# ESP32.net
KiCad netlist of a schematic drawn in EasyEDA Pro
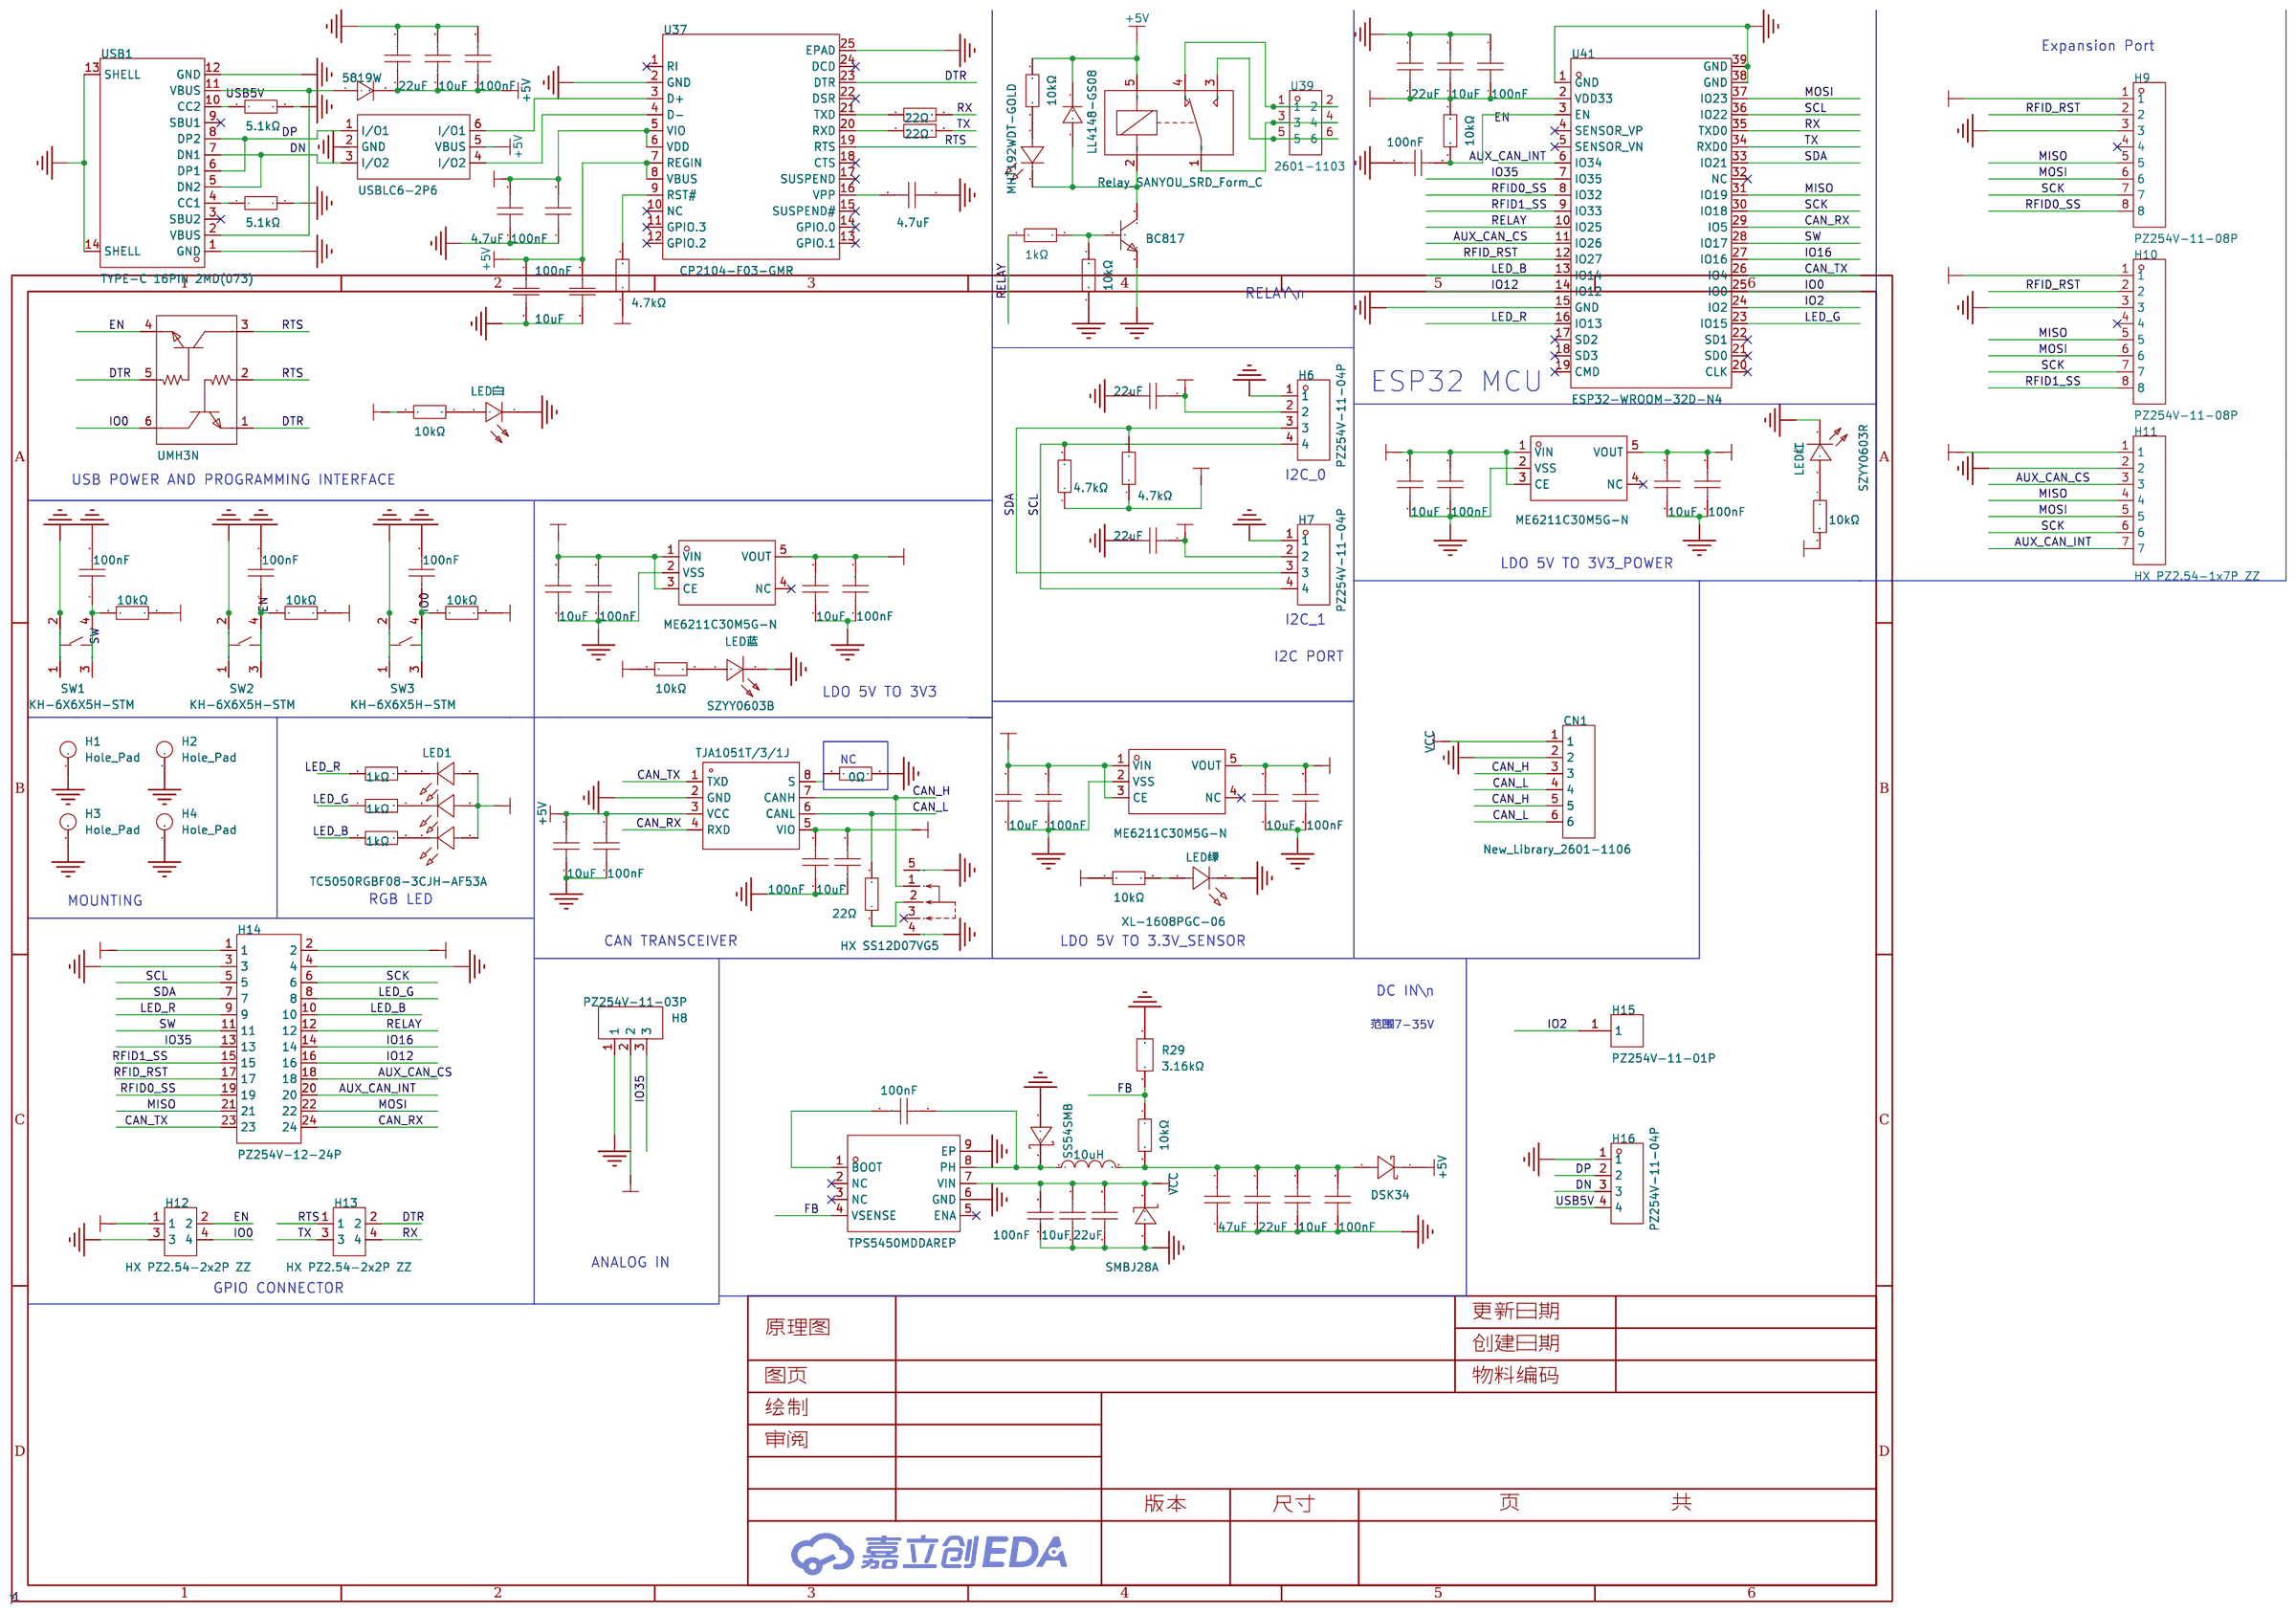
[diagram p0: schematic sheet]

(export (version "E")
  (design (tool "Eeschema 10.0.6"))
  (components
    (comp (ref "C1")
      (value "22uF")
      (footprint "easyedapro:C0805")
      (description "容值:22uF;精度:±20%;额定电压:35V;材质(温度系数):X5R;")
      (fields
        (field (name "Manufacturer Part") "CGA0805X5R226M350MT")
        (field (name "Manufacturer") "HRE(芯声)")
      )
      (libsource (lib "easyedapro") (part "CGA0805X5R226M350MT"))
    )
    (comp (ref "C2")
      (value "10uF")
      (footprint "easyedapro:C0603")
      (description "容值:10uF;精度:±20%;额定电压:25V;材质(温度系数):X5R;")
      (fields
        (field (name "Manufacturer Part") "CL10A106MA8NRNC")
        (field (name "Manufacturer") "SAMSUNG(三星)")
      )
      (libsource (lib "easyedapro") (part "CL10A106MA8NRNC"))
    )
    (comp (ref "C3")
      (value "100nF")
      (footprint "easyedapro:C0603")
      (description "容值:100nF;精度:±10%;额定电压:50V;温度系数:X7R;")
      (fields
        (field (name "Manufacturer Part") "CGA0603X7R104K500JT")
        (field (name "Manufacturer") "HRE(芯声)")
      )
      (libsource (lib "easyedapro") (part "CGA0603X7R104K500JT"))
    )
    (comp (ref "C6")
      (value "4.7uF")
      (footprint "easyedapro:C0603")
      (description "容值:4.7uF;精度:±10%;额定电压:25V;温度系数:X5R;")
      (fields
        (field (name "Manufacturer Part") "CGA0603X5R475K250JT")
        (field (name "Manufacturer") "HRE(芯声)")
      )
      (libsource (lib "easyedapro") (part "CGA0603X5R475K250JT"))
    )
    (comp (ref "C9")
      (value "100nF")
      (footprint "easyedapro:C0603")
      (description "容值:100nF;精度:±10%;额定电压:50V;温度系数:X7R;")
      (fields
        (field (name "Manufacturer Part") "CGA0603X7R104K500JT")
        (field (name "Manufacturer") "HRE(芯声)")
      )
      (libsource (lib "easyedapro") (part "CGA0603X7R104K500JT"))
    )
    (comp (ref "C10")
      (value "100nF")
      (footprint "easyedapro:C0603")
      (description "容值:100nF;精度:±10%;额定电压:50V;温度系数:X7R;")
      (fields
        (field (name "Manufacturer Part") "CGA0603X7R104K500JT")
        (field (name "Manufacturer") "HRE(芯声)")
      )
      (libsource (lib "easyedapro") (part "CGA0603X7R104K500JT"))
    )
    (comp (ref "C11")
      (value "100nF")
      (footprint "easyedapro:C0603")
      (description "容值:100nF;精度:±10%;额定电压:50V;温度系数:X7R;")
      (fields
        (field (name "Manufacturer Part") "CGA0603X7R104K500JT")
        (field (name "Manufacturer") "HRE(芯声)")
      )
      (libsource (lib "easyedapro") (part "CGA0603X7R104K500JT"))
    )
    (comp (ref "C351")
      (value "10uF")
      (footprint "easyedapro:C0603")
      (description "容值:10uF;精度:±20%;额定电压:25V;材质(温度系数):X5R;")
      (fields
        (field (name "Manufacturer Part") "CL10A106MA8NRNC")
        (field (name "Manufacturer") "SAMSUNG(三星)")
      )
      (libsource (lib "easyedapro") (part "CL10A106MA8NRNC"))
    )
    (comp (ref "C352")
      (value "10uF")
      (footprint "easyedapro:C0603")
      (description "容值:10uF;精度:±20%;额定电压:25V;材质(温度系数):X5R;")
      (fields
        (field (name "Manufacturer Part") "CL10A106MA8NRNC")
        (field (name "Manufacturer") "SAMSUNG(三星)")
      )
      (libsource (lib "easyedapro") (part "CL10A106MA8NRNC"))
    )
    (comp (ref "C353")
      (value "100nF")
      (footprint "easyedapro:C0603")
      (description "容值:100nF;精度:±10%;额定电压:50V;温度系数:X7R;")
      (fields
        (field (name "Manufacturer Part") "CGA0603X7R104K500JT")
        (field (name "Manufacturer") "HRE(芯声)")
      )
      (libsource (lib "easyedapro") (part "CGA0603X7R104K500JT"))
    )
    (comp (ref "C354")
      (value "100nF")
      (footprint "easyedapro:C0603")
      (description "容值:100nF;精度:±10%;额定电压:50V;温度系数:X7R;")
      (fields
        (field (name "Manufacturer Part") "CGA0603X7R104K500JT")
        (field (name "Manufacturer") "HRE(芯声)")
      )
      (libsource (lib "easyedapro") (part "CGA0603X7R104K500JT"))
    )
    (comp (ref "C355")
      (value "10uF")
      (footprint "easyedapro:C0603")
      (description "容值:10uF;精度:±20%;额定电压:25V;材质(温度系数):X5R;")
      (fields
        (field (name "Manufacturer Part") "CL10A106MA8NRNC")
        (field (name "Manufacturer") "SAMSUNG(三星)")
      )
      (libsource (lib "easyedapro") (part "CL10A106MA8NRNC"))
    )
    (comp (ref "C356")
      (value "100nF")
      (footprint "easyedapro:C0603")
      (description "容值:100nF;精度:±10%;额定电压:50V;温度系数:X7R;")
      (fields
        (field (name "Manufacturer Part") "CGA0603X7R104K500JT")
        (field (name "Manufacturer") "HRE(芯声)")
      )
      (libsource (lib "easyedapro") (part "CGA0603X7R104K500JT"))
    )
    (comp (ref "C357")
      (value "10uF")
      (footprint "easyedapro:C0603")
      (description "容值:10uF;精度:±20%;额定电压:25V;材质(温度系数):X5R;")
      (fields
        (field (name "Manufacturer Part") "CL10A106MA8NRNC")
        (field (name "Manufacturer") "SAMSUNG(三星)")
      )
      (libsource (lib "easyedapro") (part "CL10A106MA8NRNC"))
    )
    (comp (ref "C358")
      (value "100nF")
      (footprint "easyedapro:C0603")
      (description "容值:100nF;精度:±10%;额定电压:50V;温度系数:X7R;")
      (fields
        (field (name "Manufacturer Part") "CGA0603X7R104K500JT")
        (field (name "Manufacturer") "HRE(芯声)")
      )
      (libsource (lib "easyedapro") (part "CGA0603X7R104K500JT"))
    )
    (comp (ref "C359")
      (value "100nF")
      (footprint "easyedapro:C0603")
      (description "容值:100nF;精度:±10%;额定电压:50V;温度系数:X7R;")
      (fields
        (field (name "Manufacturer Part") "CGA0603X7R104K500JT")
        (field (name "Manufacturer") "HRE(芯声)")
      )
      (libsource (lib "easyedapro") (part "CGA0603X7R104K500JT"))
    )
    (comp (ref "C360")
      (value "4.7uF")
      (footprint "easyedapro:C0603")
      (description "容值:4.7uF;精度:±10%;额定电压:25V;温度系数:X5R;")
      (fields
        (field (name "Manufacturer Part") "CGA0603X5R475K250JT")
        (field (name "Manufacturer") "HRE(芯声)")
      )
      (libsource (lib "easyedapro") (part "CGA0603X5R475K250JT"))
    )
    (comp (ref "C361")
      (value "10uF")
      (footprint "easyedapro:C0603")
      (description "容值:10uF;精度:±20%;额定电压:25V;材质(温度系数):X5R;")
      (fields
        (field (name "Manufacturer Part") "CL10A106MA8NRNC")
        (field (name "Manufacturer") "SAMSUNG(三星)")
      )
      (libsource (lib "easyedapro") (part "CL10A106MA8NRNC"))
    )
    (comp (ref "C362")
      (value "100nF")
      (footprint "easyedapro:C0603")
      (description "容值:100nF;精度:±10%;额定电压:50V;温度系数:X7R;")
      (fields
        (field (name "Manufacturer Part") "CGA0603X7R104K500JT")
        (field (name "Manufacturer") "HRE(芯声)")
      )
      (libsource (lib "easyedapro") (part "CGA0603X7R104K500JT"))
    )
    (comp (ref "C363")
      (value "22uF")
      (footprint "easyedapro:C0805")
      (description "容值:22uF;精度:±20%;额定电压:35V;材质(温度系数):X5R;")
      (fields
        (field (name "Manufacturer Part") "CGA0805X5R226M350MT")
        (field (name "Manufacturer") "HRE(芯声)")
      )
      (libsource (lib "easyedapro") (part "CGA0805X5R226M350MT"))
    )
    (comp (ref "C364")
      (value "22uF")
      (footprint "easyedapro:C0805")
      (description "容值:22uF;精度:±20%;额定电压:35V;材质(温度系数):X5R;")
      (fields
        (field (name "Manufacturer Part") "CGA0805X5R226M350MT")
        (field (name "Manufacturer") "HRE(芯声)")
      )
      (libsource (lib "easyedapro") (part "CGA0805X5R226M350MT"))
    )
    (comp (ref "C369")
      (value "10uF")
      (footprint "easyedapro:C0603")
      (description "容值:10uF;精度:±20%;额定电压:25V;材质(温度系数):X5R;")
      (fields
        (field (name "Manufacturer Part") "CL10A106MA8NRNC")
        (field (name "Manufacturer") "SAMSUNG(三星)")
      )
      (libsource (lib "easyedapro") (part "CL10A106MA8NRNC"))
    )
    (comp (ref "C370")
      (value "10uF")
      (footprint "easyedapro:C0603")
      (description "容值:10uF;精度:±20%;额定电压:25V;材质(温度系数):X5R;")
      (fields
        (field (name "Manufacturer Part") "CL10A106MA8NRNC")
        (field (name "Manufacturer") "SAMSUNG(三星)")
      )
      (libsource (lib "easyedapro") (part "CL10A106MA8NRNC"))
    )
    (comp (ref "C371")
      (value "100nF")
      (footprint "easyedapro:C0603")
      (description "容值:100nF;精度:±10%;额定电压:50V;温度系数:X7R;")
      (fields
        (field (name "Manufacturer Part") "CGA0603X7R104K500JT")
        (field (name "Manufacturer") "HRE(芯声)")
      )
      (libsource (lib "easyedapro") (part "CGA0603X7R104K500JT"))
    )
    (comp (ref "C372")
      (value "100nF")
      (footprint "easyedapro:C0603")
      (description "容值:100nF;精度:±10%;额定电压:50V;温度系数:X7R;")
      (fields
        (field (name "Manufacturer Part") "CGA0603X7R104K500JT")
        (field (name "Manufacturer") "HRE(芯声)")
      )
      (libsource (lib "easyedapro") (part "CGA0603X7R104K500JT"))
    )
    (comp (ref "C373")
      (value "10uF")
      (footprint "easyedapro:C0603")
      (description "容值:10uF;精度:±20%;额定电压:25V;材质(温度系数):X5R;")
      (fields
        (field (name "Manufacturer Part") "CL10A106MA8NRNC")
        (field (name "Manufacturer") "SAMSUNG(三星)")
      )
      (libsource (lib "easyedapro") (part "CL10A106MA8NRNC"))
    )
    (comp (ref "C374")
      (value "100nF")
      (footprint "easyedapro:C0603")
      (description "容值:100nF;精度:±10%;额定电压:50V;温度系数:X7R;")
      (fields
        (field (name "Manufacturer Part") "CGA0603X7R104K500JT")
        (field (name "Manufacturer") "HRE(芯声)")
      )
      (libsource (lib "easyedapro") (part "CGA0603X7R104K500JT"))
    )
    (comp (ref "C375")
      (value "100nF")
      (footprint "easyedapro:C0603")
      (description "容值:100nF;精度:±10%;额定电压:50V;温度系数:X7R;")
      (fields
        (field (name "Manufacturer Part") "CGA0603X7R104K500JT")
        (field (name "Manufacturer") "HRE(芯声)")
      )
      (libsource (lib "easyedapro") (part "CGA0603X7R104K500JT"))
    )
    (comp (ref "C376")
      (value "10uF")
      (footprint "easyedapro:C0603")
      (description "容值:10uF;精度:±20%;额定电压:25V;材质(温度系数):X5R;")
      (fields
        (field (name "Manufacturer Part") "CL10A106MA8NRNC")
        (field (name "Manufacturer") "SAMSUNG(三星)")
      )
      (libsource (lib "easyedapro") (part "CL10A106MA8NRNC"))
    )
    (comp (ref "C377")
      (value "22uF")
      (footprint "easyedapro:C0805")
      (description "容值:22uF;精度:±20%;额定电压:35V;材质(温度系数):X5R;")
      (fields
        (field (name "Manufacturer Part") "CGA0805X5R226M350MT")
        (field (name "Manufacturer") "HRE(芯声)")
      )
      (libsource (lib "easyedapro") (part "CGA0805X5R226M350MT"))
    )
    (comp (ref "C378")
      (value "10uF")
      (footprint "easyedapro:C0603")
      (description "容值:10uF;精度:±20%;额定电压:25V;材质(温度系数):X5R;")
      (fields
        (field (name "Manufacturer Part") "CL10A106MA8NRNC")
        (field (name "Manufacturer") "SAMSUNG(三星)")
      )
      (libsource (lib "easyedapro") (part "CL10A106MA8NRNC"))
    )
    (comp (ref "C379")
      (value "100nF")
      (footprint "easyedapro:C0603")
      (description "容值:100nF;精度:±10%;额定电压:50V;温度系数:X7R;")
      (fields
        (field (name "Manufacturer Part") "CGA0603X7R104K500JT")
        (field (name "Manufacturer") "HRE(芯声)")
      )
      (libsource (lib "easyedapro") (part "CGA0603X7R104K500JT"))
    )
    (comp (ref "C380")
      (value "100nF")
      (footprint "easyedapro:C0603")
      (description "容值:100nF;精度:±10%;额定电压:50V;温度系数:X7R;")
      (fields
        (field (name "Manufacturer Part") "CGA0603X7R104K500JT")
        (field (name "Manufacturer") "HRE(芯声)")
      )
      (libsource (lib "easyedapro") (part "CGA0603X7R104K500JT"))
    )
    (comp (ref "C382")
      (value "10uF")
      (footprint "easyedapro:C1206")
      (description "容值:10uF;精度:±10%;额定电压:50V;温度系数:X5R;")
      (fields
        (field (name "Manufacturer Part") "HGC1206R5106K500NSPJ")
        (field (name "Manufacturer") "Chinocera(华瓷)")
      )
      (libsource (lib "easyedapro") (part "HGC1206R5106K500NSPJ"))
    )
    (comp (ref "C383")
      (value "22uF")
      (footprint "easyedapro:C1206")
      (description "容值:22uF;精度:±20%;额定电压:35V;温度系数:X5R;")
      (fields
        (field (name "Manufacturer Part") "CGA1206X5R226M350NT")
        (field (name "Manufacturer") "HRE(芯声)")
      )
      (libsource (lib "easyedapro") (part "CGA1206X5R226M350NT"))
    )
    (comp (ref "C384")
      (value "100nF")
      (footprint "easyedapro:C1206")
      (description "容值:100nF;精度:±10%;额定电压:50V;材质(温度系数):X7R;")
      (fields
        (field (name "Manufacturer Part") "CL31B104KBCNNNC")
        (field (name "Manufacturer") "SAMSUNG(三星)")
      )
      (libsource (lib "easyedapro") (part "CL31B104KBCNNNC"))
    )
    (comp (ref "C385")
      (value "47uF")
      (footprint "easyedapro:C1206")
      (description "容值:47uF;精度:±20%;额定电压:25V;温度系数:X5R;")
      (fields
        (field (name "Manufacturer Part") "HGC1206R5476M250NSPJ")
        (field (name "Manufacturer") "Chinocera(华瓷)")
      )
      (libsource (lib "easyedapro") (part "HGC1206R5476M250NSPJ"))
    )
    (comp (ref "C386")
      (value "22uF")
      (footprint "easyedapro:C0805")
      (description "容值:22uF;精度:±20%;额定电压:35V;材质(温度系数):X5R;")
      (fields
        (field (name "Manufacturer Part") "CGA0805X5R226M350MT")
        (field (name "Manufacturer") "HRE(芯声)")
      )
      (libsource (lib "easyedapro") (part "CGA0805X5R226M350MT"))
    )
    (comp (ref "C387")
      (value "10uF")
      (footprint "easyedapro:C0603")
      (description "容值:10uF;精度:±20%;额定电压:25V;材质(温度系数):X5R;")
      (fields
        (field (name "Manufacturer Part") "CL10A106MA8NRNC")
        (field (name "Manufacturer") "SAMSUNG(三星)")
      )
      (libsource (lib "easyedapro") (part "CL10A106MA8NRNC"))
    )
    (comp (ref "C388")
      (value "100nF")
      (footprint "easyedapro:C0603")
      (description "容值:100nF;精度:±10%;额定电压:50V;温度系数:X7R;")
      (fields
        (field (name "Manufacturer Part") "CGA0603X7R104K500JT")
        (field (name "Manufacturer") "HRE(芯声)")
      )
      (libsource (lib "easyedapro") (part "CGA0603X7R104K500JT"))
    )
    (comp (ref "C389")
      (value "100nF")
      (footprint "easyedapro:C0603")
      (description "容值:100nF;精度:±10%;额定电压:50V;温度系数:X7R;")
      (fields
        (field (name "Manufacturer Part") "CGA0603X7R104K500JT")
        (field (name "Manufacturer") "HRE(芯声)")
      )
      (libsource (lib "easyedapro") (part "CGA0603X7R104K500JT"))
    )
    (comp (ref "CN1")
      (value "New_Library_2601-1106")
      (footprint "easyedapro:CONN-TH_2601-1106")
      (fields (field (name "Manufacturer Part") "2601-1106"))
      (libsource (lib "easyedapro") (part "2601-1106"))
    )
    (comp (ref "D1")
      (value "USBLC6-2P6")
      (footprint "easyedapro:SOT-666-6_L1.6-W1.2-P0.50-LS1.6-BL")
      (description "极性:单向;反向截止电压(Vrwm):5V;最大钳位电压:14V;峰值脉冲电流(Ipp):5.5A;峰值脉冲功率(Ppp):80W;击穿电压:6V;")
      (fields (field (name "Manufacturer") "TECH PUBLIC(台舟)"))
      (libsource (lib "easyedapro") (part "USBLC6-2P6_C2827693"))
    )
    (comp (ref "D2")
      (value "5819W")
      (footprint "easyedapro:SOD-123_L2.7-W1.6-LS3.7-FD")
      (description "正向压降(Vf):900mV@3A;直流反向耐压(Vr):40V;整流电流:1A;")
      (fields (field (name "Manufacturer") "MOT(仁懋)"))
      (libsource (lib "easyedapro") (part "5819W"))
    )
    (comp (ref "D3")
      (value "LL4148-GS08")
      (footprint "easyedapro:SOD-80_L3.5-W1.5-RD")
      (description "二极管配置:-;正向压降(Vf):860mV@50mA;直流反向耐压(Vr):75V;整流电流:300mA;反向恢复时间(Trr):-;")
      (fields (field (name "Manufacturer") "VISHAY(威世)"))
      (libsource (lib "easyedapro") (part "LL4148-GS08"))
    )
    (comp (ref "D5")
      (value "SS54SMB")
      (footprint "easyedapro:SMB_L4.6-W3.6-LS5.3-RD")
      (description "schottky,5A 40V VF&lt;0.55V DO-214AA SMB")
      (fields (field (name "Manufacturer") "BORN(伯恩半导体)"))
      (libsource (lib "easyedapro") (part "SS54SMB"))
    )
    (comp (ref "D6")
      (value "SMBJ28A")
      (footprint "easyedapro:SMB_L4.6-W3.6-LS5.3-L-FD")
      (description "极性:Unidirectional;峰值脉冲电流（10/1000us）:13.2A;箝位电压:45.4V;击穿电压（最小值）:31.1V;反向关断电压（典型值）:28V;")
      (fields (field (name "Manufacturer") "JJW(捷捷微)"))
      (libsource (lib "easyedapro") (part "SMBJ28A_C356769"))
    )
    (comp (ref "D7")
      (value "DSK34")
      (footprint "easyedapro:SOD-123FL_L2.7-W1.8-LS3.8-RD")
      (description "二极管配置:独立式;正向压降(Vf):550mV@3A;直流反向耐压(Vr):40V;平均整流电流(Io):3A;")
      (fields (field (name "Manufacturer") "宏迦橙"))
      (libsource (lib "easyedapro") (part "DSK34_C7502709"))
    )
    (comp (ref "H1")
      (value "Hole_Pad")
      (footprint "easyedapro:MountingHole:MountingHole_3.2mm_M3_Pad_Via")
      (description "Mounting Hole with connection")
      (libsource (lib "easyedapro") (part "Mechanical_MountingHole_Pad"))
    )
    (comp (ref "H2")
      (value "Hole_Pad")
      (footprint "easyedapro:MountingHole:MountingHole_3.2mm_M3_Pad_Via")
      (description "Mounting Hole with connection")
      (libsource (lib "easyedapro") (part "Mechanical_MountingHole_Pad"))
    )
    (comp (ref "H3")
      (value "Hole_Pad")
      (footprint "easyedapro:MountingHole:MountingHole_3.2mm_M3_Pad_Via")
      (description "Mounting Hole with connection")
      (libsource (lib "easyedapro") (part "Mechanical_MountingHole_Pad"))
    )
    (comp (ref "H4")
      (value "Hole_Pad")
      (footprint "easyedapro:MountingHole:MountingHole_3.2mm_M3_Pad_Via")
      (description "Mounting Hole with connection")
      (libsource (lib "easyedapro") (part "Mechanical_MountingHole_Pad"))
    )
    (comp (ref "H6")
      (value "PZ254V-11-04P")
      (footprint "easyedapro:HDR-TH_4P-P2.54-V-M")
      (fields (field (name "Manufacturer") "XFCN(兴飞)"))
      (libsource (lib "easyedapro") (part "PZ254V-11-04P_C2691448"))
    )
    (comp (ref "H7")
      (value "PZ254V-11-04P")
      (footprint "easyedapro:HDR-TH_4P-P2.54-V-M")
      (fields (field (name "Manufacturer") "XFCN(兴飞)"))
      (libsource (lib "easyedapro") (part "PZ254V-11-04P_C2691448"))
    )
    (comp (ref "H8")
      (value "PZ254V-11-03P")
      (footprint "easyedapro:HDR-TH_3P-P2.54-V-M")
      (fields (field (name "Manufacturer") "XFCN(兴飞)"))
      (libsource (lib "easyedapro") (part "PZ254V-11-03P_C2937625"))
    )
    (comp (ref "H9")
      (value "PZ254V-11-08P")
      (footprint "easyedapro:HDR-TH_8P-P2.54-V-M")
      (fields (field (name "Manufacturer") "XFCN(兴飞)"))
      (libsource (lib "easyedapro") (part "PZ254V-11-08P"))
    )
    (comp (ref "H10")
      (value "PZ254V-11-08P")
      (footprint "easyedapro:HDR-TH_8P-P2.54-V-M")
      (fields (field (name "Manufacturer") "XFCN(兴飞)"))
      (libsource (lib "easyedapro") (part "PZ254V-11-08P"))
    )
    (comp (ref "H11")
      (value "HX PZ2.54-1x7P ZZ")
      (footprint "easyedapro:HDR-TH_7P-P2.54-V-M")
      (fields (field (name "Manufacturer") "hanxia(韩下)"))
      (libsource (lib "easyedapro") (part "HX PZ2.54-1X7P ZZ"))
    )
    (comp (ref "H12")
      (value "HX PZ2.54-2x2P ZZ")
      (footprint "easyedapro:HDR-TH_HX-PZ2.54-2X2P-ZZ")
      (fields (field (name "Manufacturer") "hanxia(韩下)"))
      (libsource (lib "easyedapro") (part "HX PZ2.54-2X2P ZZ"))
    )
    (comp (ref "H13")
      (value "HX PZ2.54-2x2P ZZ")
      (footprint "easyedapro:HDR-TH_HX-PZ2.54-2X2P-ZZ")
      (fields (field (name "Manufacturer") "hanxia(韩下)"))
      (libsource (lib "easyedapro") (part "HX PZ2.54-2X2P ZZ"))
    )
    (comp (ref "H14")
      (value "PZ254V-12-24P")
      (footprint "easyedapro:HDR-TH_24P-P2.54-V-M-R2-C12-S2.54")
      (fields (field (name "Manufacturer") "XFCN(兴飞)"))
      (libsource (lib "easyedapro") (part "PZ254V-12-24P"))
    )
    (comp (ref "H15")
      (value "PZ254V-11-01P")
      (footprint "easyedapro:HDR-TH_1P-P2.54-V-M")
      (fields (field (name "Manufacturer") "XFCN(兴飞)"))
      (libsource (lib "easyedapro") (part "PZ254V-11-01P"))
    )
    (comp (ref "H16")
      (value "PZ254V-11-04P")
      (footprint "easyedapro:HDR-TH_4P-P2.54-V-M")
      (fields (field (name "Manufacturer") "XFCN(兴飞)"))
      (libsource (lib "easyedapro") (part "PZ254V-11-04P_C2691448"))
    )
    (comp (ref "K1")
      (value "SANYOU_SRD_Form_C")
      (footprint "easyedapro:Relay_THT:Relay_SPDT_SANYOU_SRD_Series_Form_C")
      (libsource (lib "easyedapro") (part "Relay_SANYOU_SRD_Form_C"))
    )
    (comp (ref "L12")
      (value "10uH")
      (footprint "easyedapro:IND-SMD_L5.4-W5.2_FXL0530")
      (description "电感值:10uH;精度:±20%;额定电流:3.2A;饱和电流(Isat):3.5A;类型:一体成型电感;")
      (fields (field (name "Manufacturer Part") "FXL0530-100-M") (field (name "Manufacturer") "cjiang(长江微电)"))
      (libsource (lib "easyedapro") (part "FXL0530-100-M"))
    )
    (comp (ref "LED1")
      (value "TC5050RGBF08-3CJH-AF53A")
      (footprint "easyedapro:LED-SMD_6P-L5.0-W5.0-TL_TC5050RGBF08")
      (description "5050RGB，0.2W 20mA")
      (fields (field (name "Manufacturer") "TCWIN(天成)"))
      (libsource (lib "easyedapro") (part "TC5050RGBF08-3CJH-AF53A"))
    )
    (comp (ref "LED白")
      (value "NCD0603W1")
      (footprint "easyedapro:LED0603-RD")
      (fields (field (name "Manufacturer") "国星光电"))
      (libsource (lib "easyedapro") (part "NCD0603W1"))
    )
    (comp (ref "LED红")
      (value "SZYY0603R")
      (footprint "easyedapro:LED0603-R-RD")
      (fields (field (name "Manufacturer") "yongyu(永裕光电)"))
      (libsource (lib "easyedapro") (part "SZYY0603R"))
    )
    (comp (ref "LED绿")
      (value "XL-1608PGC-06")
      (footprint "easyedapro:LED0603-RD_GREEN")
      (fields (field (name "Manufacturer") "XINGLIGHT(成兴光)"))
      (libsource (lib "easyedapro") (part "XL-1608PGC-06"))
    )
    (comp (ref "LED蓝")
      (value "SZYY0603B")
      (footprint "easyedapro:LED0603-R-RD_BLUE")
      (fields (field (name "Manufacturer") "yongyu(永裕光电)"))
      (libsource (lib "easyedapro") (part "SZYY0603B"))
    )
    (comp (ref "Q1")
      (value "UMH3N")
      (footprint "easyedapro:SC-70-6_L2.2-W1.3-P0.65-LS2.1-BR")
      (description "晶体管类型:-;集射极击穿电压(Vceo):50V;集电极电流(Ic):100mA;耗散功率(Pd):150mW;直流电流增益(hFE):100@1mA,5V;")
      (fields (field (name "Manufacturer") "CJ(江苏长电/长晶)"))
      (libsource (lib "easyedapro") (part "UMH3N"))
    )
    (comp (ref "Q2")
      (value "BC817")
      (footprint "easyedapro:SOT-23-3_L2.9-W1.3-P1.90-LS2.4-BR")
      (description "晶体管类型:NPN;集电极电流(Ic):500mA;集射极击穿电压(Vceo):45V;耗散功率(Pd):300mW;直流电流增益(hFE):-;")
      (fields (field (name "Manufacturer") "JSMSEMI(杰盛微)"))
      (libsource (lib "easyedapro") (part "BC817_C916383"))
    )
    (comp (ref "R1")
      (value "5.1kΩ")
      (footprint "easyedapro:R0603")
      (description "电阻类型:厚膜电阻;阻值:5.1kΩ;精度:±1%;功率:100mW;最大工作电压:75V;温度系数:±100ppm/°C;")
      (fields
        (field (name "Manufacturer Part") "0603WAF5101T5E")
        (field (name "Manufacturer") "UNI-ROYAL(厚声)")
      )
      (libsource (lib "easyedapro") (part "0603WAF5101T5E"))
    )
    (comp (ref "R2")
      (value "5.1kΩ")
      (footprint "easyedapro:R0603")
      (description "电阻类型:厚膜电阻;阻值:5.1kΩ;精度:±1%;功率:100mW;最大工作电压:75V;温度系数:±100ppm/°C;")
      (fields
        (field (name "Manufacturer Part") "0603WAF5101T5E")
        (field (name "Manufacturer") "UNI-ROYAL(厚声)")
      )
      (libsource (lib "easyedapro") (part "0603WAF5101T5E"))
    )
    (comp (ref "R4")
      (value "22Ω")
      (footprint "easyedapro:R0603")
      (description "电阻类型:厚膜电阻;阻值:22Ω;精度:±1%;功率:100mW;最大工作电压:75V;温度系数:±100ppm/°C;")
      (fields
        (field (name "Manufacturer Part") "0603WAF220JT5E")
        (field (name "Manufacturer") "UNI-ROYAL(厚声)")
      )
      (libsource (lib "easyedapro") (part "0603WAF220JT5E"))
    )
    (comp (ref "R5")
      (value "22Ω")
      (footprint "easyedapro:R0603")
      (description "电阻类型:厚膜电阻;阻值:22Ω;精度:±1%;功率:100mW;最大工作电压:75V;温度系数:±100ppm/°C;")
      (fields
        (field (name "Manufacturer Part") "0603WAF220JT5E")
        (field (name "Manufacturer") "UNI-ROYAL(厚声)")
      )
      (libsource (lib "easyedapro") (part "0603WAF220JT5E"))
    )
    (comp (ref "R7")
      (value "10kΩ")
      (footprint "easyedapro:R0603")
      (description "电阻类型:厚膜电阻;阻值:10kΩ;精度:±1%;功率:100mW;工作电压:75V;温度系数:±100ppm/°C;")
      (fields
        (field (name "Manufacturer Part") "0603WAF1002T5E")
        (field (name "Manufacturer") "UNI-ROYAL(厚声)")
      )
      (libsource (lib "easyedapro") (part "0603WAF1002T5E"))
    )
    (comp (ref "R8")
      (value "10kΩ")
      (footprint "easyedapro:R0603")
      (description "电阻类型:厚膜电阻;阻值:10kΩ;精度:±1%;功率:100mW;工作电压:75V;温度系数:±100ppm/°C;")
      (fields
        (field (name "Manufacturer Part") "0603WAF1002T5E")
        (field (name "Manufacturer") "UNI-ROYAL(厚声)")
      )
      (libsource (lib "easyedapro") (part "0603WAF1002T5E"))
    )
    (comp (ref "R9")
      (value "10kΩ")
      (footprint "easyedapro:R0603")
      (description "电阻类型:厚膜电阻;阻值:10kΩ;精度:±1%;功率:100mW;工作电压:75V;温度系数:±100ppm/°C;")
      (fields
        (field (name "Manufacturer Part") "0603WAF1002T5E")
        (field (name "Manufacturer") "UNI-ROYAL(厚声)")
      )
      (libsource (lib "easyedapro") (part "0603WAF1002T5E"))
    )
    (comp (ref "R10")
      (value "10kΩ")
      (footprint "easyedapro:R0603")
      (description "电阻类型:厚膜电阻;阻值:10kΩ;精度:±1%;功率:100mW;工作电压:75V;温度系数:±100ppm/°C;")
      (fields
        (field (name "Manufacturer Part") "0603WAF1002T5E")
        (field (name "Manufacturer") "UNI-ROYAL(厚声)")
      )
      (libsource (lib "easyedapro") (part "0603WAF1002T5E"))
    )
    (comp (ref "R11")
      (value "10kΩ")
      (footprint "easyedapro:R0603")
      (description "电阻类型:厚膜电阻;阻值:10kΩ;精度:±1%;功率:100mW;工作电压:75V;温度系数:±100ppm/°C;")
      (fields
        (field (name "Manufacturer Part") "0603WAF1002T5E")
        (field (name "Manufacturer") "UNI-ROYAL(厚声)")
      )
      (libsource (lib "easyedapro") (part "0603WAF1002T5E"))
    )
    (comp (ref "R12")
      (value "1kΩ")
      (footprint "easyedapro:R0603")
      (description "电阻类型:厚膜电阻;阻值:1kΩ;精度:±1%;功率:100mW;最大工作电压:75V;温度系数:±100ppm/°C;")
      (fields
        (field (name "Manufacturer Part") "0603WAF1001T5E")
        (field (name "Manufacturer") "UNI-ROYAL(厚声)")
      )
      (libsource (lib "easyedapro") (part "0603WAF1001T5E"))
    )
    (comp (ref "R13")
      (value "1kΩ")
      (footprint "easyedapro:R0603")
      (description "电阻类型:厚膜电阻;阻值:1kΩ;精度:±1%;功率:100mW;最大工作电压:75V;温度系数:±100ppm/°C;")
      (fields
        (field (name "Manufacturer Part") "0603WAF1001T5E")
        (field (name "Manufacturer") "UNI-ROYAL(厚声)")
      )
      (libsource (lib "easyedapro") (part "0603WAF1001T5E"))
    )
    (comp (ref "R14")
      (value "1kΩ")
      (footprint "easyedapro:R0603")
      (description "电阻类型:厚膜电阻;阻值:1kΩ;精度:±1%;功率:100mW;最大工作电压:75V;温度系数:±100ppm/°C;")
      (fields
        (field (name "Manufacturer Part") "0603WAF1001T5E")
        (field (name "Manufacturer") "UNI-ROYAL(厚声)")
      )
      (libsource (lib "easyedapro") (part "0603WAF1001T5E"))
    )
    (comp (ref "R15")
      (value "0Ω")
      (footprint "easyedapro:R0603")
      (description "电阻类型:厚膜电阻;阻值:0Ω;精度:±1%;功率:100mW;最大工作电压:75V;")
      (fields
        (field (name "Manufacturer Part") "0603WAF0000T5E")
        (field (name "Manufacturer") "UNI-ROYAL(厚声)")
      )
      (libsource (lib "easyedapro") (part "0603WAF0000T5E"))
    )
    (comp (ref "R16")
      (value "22Ω")
      (footprint "easyedapro:R0603")
      (description "电阻类型:厚膜电阻;阻值:22Ω;精度:±1%;功率:100mW;最大工作电压:75V;温度系数:±100ppm/°C;")
      (fields
        (field (name "Manufacturer Part") "0603WAF220JT5E")
        (field (name "Manufacturer") "UNI-ROYAL(厚声)")
      )
      (libsource (lib "easyedapro") (part "0603WAF220JT5E"))
    )
    (comp (ref "R17")
      (value "4.7kΩ")
      (footprint "easyedapro:R0603")
      (description "电阻类型:厚膜电阻;阻值:4.7kΩ;精度:±1%;功率:100mW;最大工作电压:75V;温度系数:±100ppm/°C;")
      (fields
        (field (name "Manufacturer Part") "0603WAF4701T5E")
        (field (name "Manufacturer") "UNI-ROYAL(厚声)")
      )
      (libsource (lib "easyedapro") (part "0603WAF4701T5E"))
    )
    (comp (ref "R18")
      (value "10kΩ")
      (footprint "easyedapro:R0603")
      (description "电阻类型:厚膜电阻;阻值:10kΩ;精度:±1%;功率:100mW;工作电压:75V;温度系数:±100ppm/°C;")
      (fields
        (field (name "Manufacturer Part") "0603WAF1002T5E")
        (field (name "Manufacturer") "UNI-ROYAL(厚声)")
      )
      (libsource (lib "easyedapro") (part "0603WAF1002T5E"))
    )
    (comp (ref "R19")
      (value "10kΩ")
      (footprint "easyedapro:R0603")
      (description "电阻类型:厚膜电阻;阻值:10kΩ;精度:±1%;功率:100mW;工作电压:75V;温度系数:±100ppm/°C;")
      (fields
        (field (name "Manufacturer Part") "0603WAF1002T5E")
        (field (name "Manufacturer") "UNI-ROYAL(厚声)")
      )
      (libsource (lib "easyedapro") (part "0603WAF1002T5E"))
    )
    (comp (ref "R20")
      (value "1kΩ")
      (footprint "easyedapro:R0603")
      (description "电阻类型:厚膜电阻;阻值:1kΩ;精度:±1%;功率:100mW;最大工作电压:75V;温度系数:±100ppm/°C;")
      (fields
        (field (name "Manufacturer Part") "0603WAF1001T5E")
        (field (name "Manufacturer") "UNI-ROYAL(厚声)")
      )
      (libsource (lib "easyedapro") (part "0603WAF1001T5E"))
    )
    (comp (ref "R21")
      (value "4.7kΩ")
      (footprint "easyedapro:R0603")
      (description "电阻类型:厚膜电阻;阻值:4.7kΩ;精度:±1%;功率:100mW;最大工作电压:75V;温度系数:±100ppm/°C;")
      (fields
        (field (name "Manufacturer Part") "0603WAF4701T5E")
        (field (name "Manufacturer") "UNI-ROYAL(厚声)")
      )
      (libsource (lib "easyedapro") (part "0603WAF4701T5E"))
    )
    (comp (ref "R22")
      (value "4.7kΩ")
      (footprint "easyedapro:R0603")
      (description "电阻类型:厚膜电阻;阻值:4.7kΩ;精度:±1%;功率:100mW;最大工作电压:75V;温度系数:±100ppm/°C;")
      (fields
        (field (name "Manufacturer Part") "0603WAF4701T5E")
        (field (name "Manufacturer") "UNI-ROYAL(厚声)")
      )
      (libsource (lib "easyedapro") (part "0603WAF4701T5E"))
    )
    (comp (ref "R23")
      (value "10kΩ")
      (footprint "easyedapro:R0603")
      (description "电阻类型:厚膜电阻;阻值:10kΩ;精度:±1%;功率:100mW;工作电压:75V;温度系数:±100ppm/°C;")
      (fields
        (field (name "Manufacturer Part") "0603WAF1002T5E")
        (field (name "Manufacturer") "UNI-ROYAL(厚声)")
      )
      (libsource (lib "easyedapro") (part "0603WAF1002T5E"))
    )
    (comp (ref "R24")
      (value "10kΩ")
      (footprint "easyedapro:R0603")
      (description "电阻类型:厚膜电阻;阻值:10kΩ;精度:±1%;功率:100mW;工作电压:75V;温度系数:±100ppm/°C;")
      (fields
        (field (name "Manufacturer Part") "0603WAF1002T5E")
        (field (name "Manufacturer") "UNI-ROYAL(厚声)")
      )
      (libsource (lib "easyedapro") (part "0603WAF1002T5E"))
    )
    (comp (ref "R25")
      (value "10kΩ")
      (footprint "easyedapro:R0603")
      (description "电阻类型:厚膜电阻;阻值:10kΩ;精度:±1%;功率:100mW;工作电压:75V;温度系数:±100ppm/°C;")
      (fields
        (field (name "Manufacturer Part") "0603WAF1002T5E")
        (field (name "Manufacturer") "UNI-ROYAL(厚声)")
      )
      (libsource (lib "easyedapro") (part "0603WAF1002T5E"))
    )
    (comp (ref "R28")
      (value "10kΩ")
      (footprint "easyedapro:R0603")
      (description "电阻类型:厚膜电阻;阻值:10kΩ;精度:±1%;功率:100mW;工作电压:75V;温度系数:±100ppm/°C;")
      (fields
        (field (name "Manufacturer Part") "0603WAF1002T5E")
        (field (name "Manufacturer") "UNI-ROYAL(厚声)")
      )
      (libsource (lib "easyedapro") (part "0603WAF1002T5E"))
    )
    (comp (ref "R29")
      (value "3.16kΩ")
      (footprint "easyedapro:R0603")
      (description "电阻类型:厚膜电阻;阻值:3.16kΩ;精度:±1%;功率:100mW;最大工作电压:75V;温度系数:±100ppm/°C;")
      (fields (field (name "Manufacturer Part") "FRC0603F3161TS") (field (name "Manufacturer") "FOJAN(富捷)"))
      (libsource (lib "easyedapro") (part "FRC0603F3161TS"))
    )
    (comp (ref "SW1")
      (value "KH-6X6X5H-STM")
      (footprint "easyedapro:SW-SMD_4P-L6.0-W6.0-P4.50-LS9.0_H5.0")
      (description "电路结构:单刀单掷;按钮形状:圆形按钮;安装方式:立贴;开关长度:6mm;开关宽度:6mm;开关高度:5mm;带支架:不带;触点电流:50mA;额定电压(DC):12V;机械寿命:8万次;")
      (fields (field (name "Manufacturer") "kinghelm(金航标)"))
      (libsource (lib "easyedapro") (part "KH-6X6X5H-STM"))
    )
    (comp (ref "SW2")
      (value "KH-6X6X5H-STM")
      (footprint "easyedapro:SW-SMD_4P-L6.0-W6.0-P4.50-LS9.0_H5.0")
      (description "电路结构:单刀单掷;按钮形状:圆形按钮;安装方式:立贴;开关长度:6mm;开关宽度:6mm;开关高度:5mm;带支架:不带;触点电流:50mA;额定电压(DC):12V;机械寿命:8万次;")
      (fields (field (name "Manufacturer") "kinghelm(金航标)"))
      (libsource (lib "easyedapro") (part "KH-6X6X5H-STM"))
    )
    (comp (ref "SW3")
      (value "KH-6X6X5H-STM")
      (footprint "easyedapro:SW-SMD_4P-L6.0-W6.0-P4.50-LS9.0_H5.0")
      (description "电路结构:单刀单掷;按钮形状:圆形按钮;安装方式:立贴;开关长度:6mm;开关宽度:6mm;开关高度:5mm;带支架:不带;触点电流:50mA;额定电压(DC):12V;机械寿命:8万次;")
      (fields (field (name "Manufacturer") "kinghelm(金航标)"))
      (libsource (lib "easyedapro") (part "KH-6X6X5H-STM"))
    )
    (comp (ref "U31")
      (value "ME6211C30M5G-N")
      (footprint "easyedapro:SOT-23-5_L2.9-W1.6-P0.95-LS2.8-BL")
      (description "输出类型:固定;最大输入电压:6V;输出电压:3V;最大输出电流:500mA;电源纹波抑制比(PSRR):-;输出极性:正极;")
      (fields (field (name "Manufacturer") "MICRONE(南京微盟)"))
      (libsource (lib "easyedapro") (part "ME6211C30M5G-N"))
    )
    (comp (ref "U34")
      (value "TJA1051T/3/1J")
      (footprint "easyedapro:SOIC-8_L4.9-W3.9-P1.27-LS6.0-BL")
      (description "类型:-;数据速率:5Mbps;")
      (fields (field (name "Manufacturer") "NXP(恩智浦)"))
      (libsource (lib "easyedapro") (part "TJA1051T/3/1J"))
    )
    (comp (ref "U36")
      (value "HX SS12D07VG5")
      (footprint "easyedapro:SW-TH_SS12D07VG3")
      (description "电路结构:单刀双掷;安装方式:直插;开关颜色:黑色;额定电流:300mA;额定电压:50V;工作寿命:1万次;")
      (fields (field (name "Manufacturer") "hanxia(韩下)"))
      (libsource (lib "easyedapro") (part "HX SS12D07VG5"))
    )
    (comp (ref "U37")
      (value "CP2104-F03-GMR")
      (footprint "easyedapro:QFN-24_L4.0-W4.0-P0.50-BL-EP2.7")
      (description "应用功能:USB转UART;接口协议:-;数据速率:2Mbps;")
      (fields (field (name "Manufacturer") "SKYWORKS/SILICON LABS(芯科)"))
      (libsource (lib "easyedapro") (part "CP2104-F03-GM"))
    )
    (comp (ref "U38")
      (value "MHT192WDT-GOLD")
      (footprint "easyedapro:LED0603-RD-YELLOW")
      (description "发光颜色:黄色;功率:60mW;正向电流:5mA;主波长:-;二极管配置:-;透镜颜色:雾状黄透镜;色温:-;发光角度:130°;载带方式:-;工作温度:-40°C~+85°C;")
      (fields (field (name "Manufacturer") "MEIHUA(美华)"))
      (libsource (lib "easyedapro") (part "MHT192WDT-GOLD"))
    )
    (comp (ref "U39")
      (value "2601-1103")
      (footprint "easyedapro:CONN-TH_6P-P3.50_2601-1103")
      (description "PCB 接线端子; 操作手柄; 1.5 mm2; 焊针间距 3.5 mm; 3极; 推入式笼夹; 1,50 mm2; 灰色")
      (fields (field (name "Manufacturer") "WAGO(万可)"))
      (libsource (lib "easyedapro") (part "2601-1103"))
    )
    (comp (ref "U40")
      (value "ME6211C30M5G-N")
      (footprint "easyedapro:SOT-23-5_L2.9-W1.6-P0.95-LS2.8-BL")
      (description "输出类型:固定;最大输入电压:6V;输出电压:3V;最大输出电流:500mA;电源纹波抑制比(PSRR):-;输出极性:正极;")
      (fields (field (name "Manufacturer") "MICRONE(南京微盟)"))
      (libsource (lib "easyedapro") (part "ME6211C30M5G-N"))
    )
    (comp (ref "U41")
      (value "ESP32-WROOM-32D-N4")
      (footprint "easyedapro:WIFIM-SMD_39P-L25.5-W18.0-P1.27-BL")
      (description "ESP32-WROOM-32D 集成 ESP32-D0WD，功能强大，用途广泛，可以用于低功耗传感器网络和要求极高的任务，例如语音编码、音频流和 MP3 解码等。")
      (fields (field (name "Manufacturer") "ESPRESSIF(乐鑫)"))
      (libsource (lib "easyedapro") (part "ESP32-WROOM-32D"))
    )
    (comp (ref "U42")
      (value "ME6211C30M5G-N")
      (footprint "easyedapro:SOT-23-5_L2.9-W1.6-P0.95-LS2.8-BL")
      (description "输出类型:固定;最大输入电压:6V;输出电压:3V;最大输出电流:500mA;电源纹波抑制比(PSRR):-;输出极性:正极;")
      (fields (field (name "Manufacturer") "MICRONE(南京微盟)"))
      (libsource (lib "easyedapro") (part "ME6211C30M5G-N"))
    )
    (comp (ref "U43")
      (value "TPS5450MDDAREP")
      (footprint "easyedapro:POWERPAD-SO-8_L4.9-W3.9-P1.27-LS6.0-BL-EP")
      (description "功能类型:降压型;输出类型:可调;工作电压:5.5V~36V;输出电压:1.221V~32.04V;输出电流:5A;")
      (fields (field (name "Manufacturer") "TI(德州仪器)"))
      (libsource (lib "easyedapro") (part "TPS5450MDDAREP"))
    )
    (comp (ref "USB1")
      (value "TYPE-C 16PIN 2MD(073)")
      (footprint "easyedapro:USB-C-SMD_TYPE-C-6PIN-2MD-073")
      (description "连接器类型:Type-C;协议标准:USB 3.1;公母:母;安装方式:卧贴;触点数量:16P;端口数量:1;额定电流 - 电源:3A;工作温度:-25°C~+85°C;")
      (fields (field (name "Manufacturer") "SHOU HAN(首韩)"))
      (libsource (lib "easyedapro") (part "TYPE-C 16PIN 2MD(073)"))
    )
  )
  (nets
    (net (code "1") (name "+5V") (class "Default")
      (node (ref "C1") (pin "1") (pinfunction "1_1") (pintype "unspecified"))
      (node (ref "C2") (pin "1") (pinfunction "1_1") (pintype "unspecified"))
      (node (ref "C3") (pin "1") (pinfunction "1_1") (pintype "unspecified"))
      (node (ref "C351") (pin "2") (pinfunction "2_2") (pintype "unspecified"))
      (node (ref "C353") (pin "2") (pinfunction "2_2") (pintype "unspecified"))
      (node (ref "C355") (pin "2") (pinfunction "2_2") (pintype "unspecified"))
      (node (ref "C356") (pin "2") (pinfunction "2_2") (pintype "unspecified"))
      (node (ref "C361") (pin "2") (pinfunction "2_2") (pintype "unspecified"))
      (node (ref "C362") (pin "2") (pinfunction "2_2") (pintype "unspecified"))
      (node (ref "C369") (pin "2") (pinfunction "2_2") (pintype "unspecified"))
      (node (ref "C371") (pin "2") (pinfunction "2_2") (pintype "unspecified"))
      (node (ref "C374") (pin "2") (pinfunction "2_2") (pintype "unspecified"))
      (node (ref "C376") (pin "2") (pinfunction "2_2") (pintype "unspecified"))
      (node (ref "D1") (pin "5") (pinfunction "VBUS_5") (pintype "unspecified"))
      (node (ref "D2") (pin "2") (pinfunction "C_2") (pintype "unspecified"))
      (node (ref "D3") (pin "1") (pinfunction "C_1") (pintype "unspecified"))
      (node (ref "D7") (pin "1") (pinfunction "K_1") (pintype "input"))
      (node (ref "H14") (pin "1") (pinfunction "1_1") (pintype "unspecified"))
      (node (ref "K1") (pin "5") (pinfunction "~_5") (pintype "unspecified"))
      (node (ref "R18") (pin "1") (pinfunction "1_1") (pintype "input"))
      (node (ref "U31") (pin "1") (pinfunction "VIN_1") (pintype "unspecified"))
      (node (ref "U31") (pin "3") (pinfunction "CE_3") (pintype "unspecified"))
      (node (ref "U34") (pin "3") (pinfunction "VCC_3") (pintype "unspecified"))
      (node (ref "U37") (pin "7") (pinfunction "REGIN_7") (pintype "unspecified"))
      (node (ref "U37") (pin "8") (pinfunction "VBUS_8") (pintype "unspecified"))
      (node (ref "U40") (pin "1") (pinfunction "VIN_1") (pintype "unspecified"))
      (node (ref "U40") (pin "3") (pinfunction "CE_3") (pintype "unspecified"))
      (node (ref "U42") (pin "1") (pinfunction "VIN_1") (pintype "unspecified"))
      (node (ref "U42") (pin "3") (pinfunction "CE_3") (pintype "unspecified"))
    )
    (net (code "2") (name "/AUX_CAN_CS") (class "Default")
      (node (ref "H11") (pin "3") (pinfunction "3_3") (pintype "unspecified"))
      (node (ref "H14") (pin "18") (pinfunction "18_18") (pintype "unspecified"))
      (node (ref "U41") (pin "11") (pinfunction "IO26_11") (pintype "unspecified"))
    )
    (net (code "3") (name "/AUX_CAN_INT") (class "Default")
      (node (ref "H11") (pin "7") (pinfunction "7_7") (pintype "unspecified"))
      (node (ref "H14") (pin "20") (pinfunction "20_20") (pintype "unspecified"))
      (node (ref "U41") (pin "6") (pinfunction "IO34_6") (pintype "unspecified"))
    )
    (net (code "4") (name "/CAN_H") (class "Default")
      (node (ref "CN1") (pin "3") (pinfunction "3_3") (pintype "unspecified"))
      (node (ref "CN1") (pin "5") (pinfunction "5_5") (pintype "unspecified"))
      (node (ref "U34") (pin "7") (pinfunction "CANH_7") (pintype "unspecified"))
      (node (ref "U36") (pin "1") (pinfunction "1_1") (pintype "unspecified"))
    )
    (net (code "5") (name "/CAN_L") (class "Default")
      (node (ref "CN1") (pin "4") (pinfunction "4_4") (pintype "unspecified"))
      (node (ref "CN1") (pin "6") (pinfunction "6_6") (pintype "unspecified"))
      (node (ref "R16") (pin "2") (pinfunction "2_2") (pintype "input"))
      (node (ref "U34") (pin "6") (pinfunction "CANL_6") (pintype "unspecified"))
    )
    (net (code "6") (name "/CAN_RX") (class "Default")
      (node (ref "H14") (pin "24") (pinfunction "24_24") (pintype "unspecified"))
      (node (ref "U34") (pin "4") (pinfunction "RXD_4") (pintype "unspecified"))
      (node (ref "U41") (pin "29") (pinfunction "IO5_29") (pintype "unspecified"))
    )
    (net (code "7") (name "/CAN_TX") (class "Default")
      (node (ref "H14") (pin "23") (pinfunction "23_23") (pintype "unspecified"))
      (node (ref "U34") (pin "1") (pinfunction "TXD_1") (pintype "unspecified"))
      (node (ref "U41") (pin "26") (pinfunction "IO4_26") (pintype "unspecified"))
    )
    (net (code "8") (name "/DN") (class "Default")
      (node (ref "D1") (pin "3") (pinfunction "I/O2_3") (pintype "unspecified"))
      (node (ref "H16") (pin "3") (pinfunction "3_3") (pintype "unspecified"))
      (node (ref "USB1") (pin "5") (pinfunction "DN2_5") (pintype "unspecified"))
      (node (ref "USB1") (pin "7") (pinfunction "DN1_7") (pintype "unspecified"))
    )
    (net (code "9") (name "/DP") (class "Default")
      (node (ref "D1") (pin "1") (pinfunction "I/O1_1") (pintype "unspecified"))
      (node (ref "H16") (pin "2") (pinfunction "2_2") (pintype "unspecified"))
      (node (ref "USB1") (pin "6") (pinfunction "DP1_6") (pintype "unspecified"))
      (node (ref "USB1") (pin "8") (pinfunction "DP2_8") (pintype "unspecified"))
    )
    (net (code "10") (name "/DTR") (class "Default")
      (node (ref "H13") (pin "2") (pinfunction "2_2") (pintype "unspecified"))
      (node (ref "Q1") (pin "1") (pinfunction "E_1") (pintype "unspecified"))
      (node (ref "Q1") (pin "5") (pinfunction "B_5") (pintype "unspecified"))
      (node (ref "U37") (pin "23") (pinfunction "DTR_23") (pintype "unspecified"))
    )
    (net (code "11") (name "/EN") (class "Default")
      (node (ref "C10") (pin "1") (pinfunction "1_1") (pintype "unspecified"))
      (node (ref "C380") (pin "1") (pinfunction "1_1") (pintype "unspecified"))
      (node (ref "H12") (pin "2") (pinfunction "2_2") (pintype "unspecified"))
      (node (ref "Q1") (pin "4") (pinfunction "E_4") (pintype "unspecified"))
      (node (ref "R25") (pin "2") (pinfunction "2_2") (pintype "input"))
      (node (ref "R9") (pin "1") (pinfunction "1_1") (pintype "input"))
      (node (ref "SW2") (pin "3") (pinfunction "3_3") (pintype "unspecified"))
      (node (ref "SW2") (pin "4") (pinfunction "4_4") (pintype "unspecified"))
      (node (ref "U41") (pin "3") (pinfunction "EN_3") (pintype "unspecified"))
    )
    (net (code "12") (name "/FB") (class "Default")
      (node (ref "R28") (pin "1") (pinfunction "1_1") (pintype "input"))
      (node (ref "R29") (pin "1") (pinfunction "1_1") (pintype "unspecified"))
      (node (ref "U43") (pin "4") (pinfunction "VSENSE_4") (pintype "unspecified"))
    )
    (net (code "13") (name "/IO0") (class "Default")
      (node (ref "C11") (pin "1") (pinfunction "1_1") (pintype "unspecified"))
      (node (ref "H12") (pin "4") (pinfunction "4_4") (pintype "unspecified"))
      (node (ref "Q1") (pin "6") (pinfunction "C_6") (pintype "unspecified"))
      (node (ref "R10") (pin "1") (pinfunction "1_1") (pintype "input"))
      (node (ref "SW3") (pin "3") (pinfunction "3_3") (pintype "unspecified"))
      (node (ref "SW3") (pin "4") (pinfunction "4_4") (pintype "unspecified"))
      (node (ref "U41") (pin "25") (pinfunction "IO0_25") (pintype "unspecified"))
    )
    (net (code "14") (name "/IO2") (class "Default")
      (node (ref "H15") (pin "1") (pinfunction "1_1") (pintype "unspecified"))
      (node (ref "U41") (pin "24") (pinfunction "IO2_24") (pintype "unspecified"))
    )
    (net (code "15") (name "/IO12") (class "Default")
      (node (ref "H14") (pin "16") (pinfunction "16_16") (pintype "unspecified"))
      (node (ref "U41") (pin "14") (pinfunction "IO12_14") (pintype "unspecified"))
    )
    (net (code "16") (name "/IO16") (class "Default")
      (node (ref "H14") (pin "14") (pinfunction "14_14") (pintype "unspecified"))
      (node (ref "U41") (pin "27") (pinfunction "IO16_27") (pintype "unspecified"))
    )
    (net (code "17") (name "/IO35") (class "Default")
      (node (ref "H14") (pin "13") (pinfunction "13_13") (pintype "unspecified"))
      (node (ref "H8") (pin "3") (pinfunction "3_3") (pintype "unspecified"))
      (node (ref "U41") (pin "7") (pinfunction "IO35_7") (pintype "unspecified"))
    )
    (net (code "18") (name "/LED_B") (class "Default")
      (node (ref "H14") (pin "10") (pinfunction "10_10") (pintype "unspecified"))
      (node (ref "R14") (pin "1") (pinfunction "1_1") (pintype "input"))
      (node (ref "U41") (pin "13") (pinfunction "IO14_13") (pintype "unspecified"))
    )
    (net (code "19") (name "/LED_G") (class "Default")
      (node (ref "H14") (pin "8") (pinfunction "8_8") (pintype "unspecified"))
      (node (ref "R13") (pin "1") (pinfunction "1_1") (pintype "input"))
      (node (ref "U41") (pin "23") (pinfunction "IO15_23") (pintype "unspecified"))
    )
    (net (code "20") (name "/LED_R") (class "Default")
      (node (ref "H14") (pin "9") (pinfunction "9_9") (pintype "unspecified"))
      (node (ref "R12") (pin "1") (pinfunction "1_1") (pintype "input"))
      (node (ref "U41") (pin "16") (pinfunction "IO13_16") (pintype "unspecified"))
    )
    (net (code "21") (name "/MISO") (class "Default")
      (node (ref "H10") (pin "5") (pinfunction "5_5") (pintype "unspecified"))
      (node (ref "H11") (pin "4") (pinfunction "4_4") (pintype "unspecified"))
      (node (ref "H14") (pin "21") (pinfunction "21_21") (pintype "unspecified"))
      (node (ref "H9") (pin "5") (pinfunction "5_5") (pintype "unspecified"))
      (node (ref "U41") (pin "31") (pinfunction "IO19_31") (pintype "unspecified"))
    )
    (net (code "22") (name "/MOSI") (class "Default")
      (node (ref "H10") (pin "6") (pinfunction "6_6") (pintype "unspecified"))
      (node (ref "H11") (pin "5") (pinfunction "5_5") (pintype "unspecified"))
      (node (ref "H14") (pin "22") (pinfunction "22_22") (pintype "unspecified"))
      (node (ref "H9") (pin "6") (pinfunction "6_6") (pintype "unspecified"))
      (node (ref "U41") (pin "37") (pinfunction "IO23_37") (pintype "unspecified"))
    )
    (net (code "23") (name "/RELAY") (class "Default")
      (node (ref "H14") (pin "12") (pinfunction "12_12") (pintype "unspecified"))
      (node (ref "R20") (pin "1") (pinfunction "1_1") (pintype "input"))
      (node (ref "U41") (pin "10") (pinfunction "IO25_10") (pintype "unspecified"))
    )
    (net (code "24") (name "/RFID0_SS") (class "Default")
      (node (ref "H14") (pin "19") (pinfunction "19_19") (pintype "unspecified"))
      (node (ref "H9") (pin "8") (pinfunction "8_8") (pintype "unspecified"))
      (node (ref "U41") (pin "8") (pinfunction "IO32_8") (pintype "unspecified"))
    )
    (net (code "25") (name "/RFID1_SS") (class "Default")
      (node (ref "H10") (pin "8") (pinfunction "8_8") (pintype "unspecified"))
      (node (ref "H14") (pin "15") (pinfunction "15_15") (pintype "unspecified"))
      (node (ref "U41") (pin "9") (pinfunction "IO33_9") (pintype "unspecified"))
    )
    (net (code "26") (name "/RFID_RST") (class "Default")
      (node (ref "H10") (pin "2") (pinfunction "2_2") (pintype "unspecified"))
      (node (ref "H14") (pin "17") (pinfunction "17_17") (pintype "unspecified"))
      (node (ref "H9") (pin "2") (pinfunction "2_2") (pintype "unspecified"))
      (node (ref "U41") (pin "12") (pinfunction "IO27_12") (pintype "unspecified"))
    )
    (net (code "27") (name "/RTS") (class "Default")
      (node (ref "H13") (pin "1") (pinfunction "1_1") (pintype "unspecified"))
      (node (ref "Q1") (pin "2") (pinfunction "B_2") (pintype "unspecified"))
      (node (ref "Q1") (pin "3") (pinfunction "C_3") (pintype "unspecified"))
      (node (ref "U37") (pin "19") (pinfunction "RTS_19") (pintype "unspecified"))
    )
    (net (code "28") (name "/RX") (class "Default")
      (node (ref "H13") (pin "4") (pinfunction "4_4") (pintype "unspecified"))
      (node (ref "R4") (pin "2") (pinfunction "2_2") (pintype "input"))
      (node (ref "U41") (pin "35") (pinfunction "TXD0_35") (pintype "unspecified"))
    )
    (net (code "29") (name "/SCK") (class "Default")
      (node (ref "H10") (pin "7") (pinfunction "7_7") (pintype "unspecified"))
      (node (ref "H11") (pin "6") (pinfunction "6_6") (pintype "unspecified"))
      (node (ref "H14") (pin "6") (pinfunction "6_6") (pintype "unspecified"))
      (node (ref "H9") (pin "7") (pinfunction "7_7") (pintype "unspecified"))
      (node (ref "U41") (pin "30") (pinfunction "IO18_30") (pintype "unspecified"))
    )
    (net (code "30") (name "/SCL") (class "Default")
      (node (ref "H14") (pin "5") (pinfunction "5_5") (pintype "unspecified"))
      (node (ref "H6") (pin "4") (pinfunction "4_4") (pintype "unspecified"))
      (node (ref "H7") (pin "4") (pinfunction "4_4") (pintype "unspecified"))
      (node (ref "R21") (pin "2") (pinfunction "2_2") (pintype "input"))
      (node (ref "U41") (pin "36") (pinfunction "IO22_36") (pintype "unspecified"))
    )
    (net (code "31") (name "/SDA") (class "Default")
      (node (ref "H14") (pin "7") (pinfunction "7_7") (pintype "unspecified"))
      (node (ref "H6") (pin "3") (pinfunction "3_3") (pintype "unspecified"))
      (node (ref "H7") (pin "3") (pinfunction "3_3") (pintype "unspecified"))
      (node (ref "R22") (pin "2") (pinfunction "2_2") (pintype "input"))
      (node (ref "U41") (pin "33") (pinfunction "IO21_33") (pintype "unspecified"))
    )
    (net (code "32") (name "/SW") (class "Default")
      (node (ref "C9") (pin "1") (pinfunction "1_1") (pintype "unspecified"))
      (node (ref "H14") (pin "11") (pinfunction "11_11") (pintype "unspecified"))
      (node (ref "R8") (pin "1") (pinfunction "1_1") (pintype "input"))
      (node (ref "SW1") (pin "3") (pinfunction "3_3") (pintype "unspecified"))
      (node (ref "SW1") (pin "4") (pinfunction "4_4") (pintype "unspecified"))
      (node (ref "U41") (pin "28") (pinfunction "IO17_28") (pintype "unspecified"))
    )
    (net (code "33") (name "/TX") (class "Default")
      (node (ref "H13") (pin "3") (pinfunction "3_3") (pintype "unspecified"))
      (node (ref "R5") (pin "2") (pinfunction "2_2") (pintype "input"))
      (node (ref "U41") (pin "34") (pinfunction "RXD0_34") (pintype "unspecified"))
    )
    (net (code "34") (name "/USB5V") (class "Default")
      (node (ref "D2") (pin "1") (pinfunction "A_1") (pintype "unspecified"))
      (node (ref "H16") (pin "4") (pinfunction "4_4") (pintype "unspecified"))
      (node (ref "USB1") (pin "11") (pinfunction "VBUS_11") (pintype "unspecified"))
      (node (ref "USB1") (pin "2") (pinfunction "VBUS_2") (pintype "unspecified"))
    )
    (net (code "35") (name "3.3_SENSOR") (class "Default")
      (node (ref "C363") (pin "1") (pinfunction "1_1") (pintype "unspecified"))
      (node (ref "C364") (pin "1") (pinfunction "1_1") (pintype "unspecified"))
      (node (ref "C370") (pin "2") (pinfunction "2_2") (pintype "unspecified"))
      (node (ref "C372") (pin "2") (pinfunction "2_2") (pintype "unspecified"))
      (node (ref "H10") (pin "1") (pinfunction "1_1") (pintype "unspecified"))
      (node (ref "H11") (pin "1") (pinfunction "1_1") (pintype "unspecified"))
      (node (ref "H6") (pin "2") (pinfunction "2_2") (pintype "unspecified"))
      (node (ref "H7") (pin "2") (pinfunction "2_2") (pintype "unspecified"))
      (node (ref "H8") (pin "2") (pinfunction "2_2") (pintype "unspecified"))
      (node (ref "H9") (pin "1") (pinfunction "1_1") (pintype "unspecified"))
      (node (ref "R21") (pin "1") (pinfunction "1_1") (pintype "input"))
      (node (ref "R22") (pin "1") (pinfunction "1_1") (pintype "input"))
      (node (ref "R23") (pin "2") (pinfunction "2_2") (pintype "input"))
      (node (ref "U40") (pin "5") (pinfunction "VOUT_5") (pintype "unspecified"))
    )
    (net (code "36") (name "3V3") (class "Default")
      (node (ref "C352") (pin "2") (pinfunction "2_2") (pintype "unspecified"))
      (node (ref "C354") (pin "2") (pinfunction "2_2") (pintype "unspecified"))
      (node (ref "C357") (pin "2") (pinfunction "2_2") (pintype "unspecified"))
      (node (ref "C358") (pin "2") (pinfunction "2_2") (pintype "unspecified"))
      (node (ref "H12") (pin "1") (pinfunction "1_1") (pintype "unspecified"))
      (node (ref "H14") (pin "2") (pinfunction "2_2") (pintype "unspecified"))
      (node (ref "LED1") (pin "1") (pinfunction "+_1") (pintype "unspecified"))
      (node (ref "LED1") (pin "2") (pinfunction "+_2") (pintype "unspecified"))
      (node (ref "LED1") (pin "3") (pinfunction "+_3") (pintype "unspecified"))
      (node (ref "R10") (pin "2") (pinfunction "2_2") (pintype "input"))
      (node (ref "R11") (pin "2") (pinfunction "2_2") (pintype "input"))
      (node (ref "R8") (pin "2") (pinfunction "2_2") (pintype "input"))
      (node (ref "R9") (pin "2") (pinfunction "2_2") (pintype "input"))
      (node (ref "U31") (pin "5") (pinfunction "VOUT_5") (pintype "unspecified"))
      (node (ref "U34") (pin "5") (pinfunction "VIO_5") (pintype "unspecified"))
    )
    (net (code "37") (name "3V3_POWER") (class "Default")
      (node (ref "C373") (pin "2") (pinfunction "2_2") (pintype "unspecified"))
      (node (ref "C375") (pin "2") (pinfunction "2_2") (pintype "unspecified"))
      (node (ref "C377") (pin "1") (pinfunction "1_1") (pintype "unspecified"))
      (node (ref "C378") (pin "1") (pinfunction "1_1") (pintype "unspecified"))
      (node (ref "C379") (pin "1") (pinfunction "1_1") (pintype "unspecified"))
      (node (ref "R24") (pin "2") (pinfunction "2_2") (pintype "input"))
      (node (ref "R25") (pin "1") (pinfunction "1_1") (pintype "input"))
      (node (ref "U41") (pin "2") (pinfunction "VDD33_2") (pintype "unspecified"))
      (node (ref "U42") (pin "5") (pinfunction "VOUT_5") (pintype "unspecified"))
    )
    (net (code "38") (name "GND") (class "Default")
      (node (ref "C1") (pin "2") (pinfunction "2_2") (pintype "unspecified"))
      (node (ref "C10") (pin "2") (pinfunction "2_2") (pintype "unspecified"))
      (node (ref "C11") (pin "2") (pinfunction "2_2") (pintype "unspecified"))
      (node (ref "C2") (pin "2") (pinfunction "2_2") (pintype "unspecified"))
      (node (ref "C3") (pin "2") (pinfunction "2_2") (pintype "unspecified"))
      (node (ref "C351") (pin "1") (pinfunction "1_1") (pintype "unspecified"))
      (node (ref "C352") (pin "1") (pinfunction "1_1") (pintype "unspecified"))
      (node (ref "C353") (pin "1") (pinfunction "1_1") (pintype "unspecified"))
      (node (ref "C354") (pin "1") (pinfunction "1_1") (pintype "unspecified"))
      (node (ref "C355") (pin "1") (pinfunction "1_1") (pintype "unspecified"))
      (node (ref "C356") (pin "1") (pinfunction "1_1") (pintype "unspecified"))
      (node (ref "C357") (pin "1") (pinfunction "1_1") (pintype "unspecified"))
      (node (ref "C358") (pin "1") (pinfunction "1_1") (pintype "unspecified"))
      (node (ref "C359") (pin "1") (pinfunction "1_1") (pintype "unspecified"))
      (node (ref "C360") (pin "1") (pinfunction "1_1") (pintype "unspecified"))
      (node (ref "C361") (pin "1") (pinfunction "1_1") (pintype "unspecified"))
      (node (ref "C362") (pin "1") (pinfunction "1_1") (pintype "unspecified"))
      (node (ref "C363") (pin "2") (pinfunction "2_2") (pintype "unspecified"))
      (node (ref "C364") (pin "2") (pinfunction "2_2") (pintype "unspecified"))
      (node (ref "C369") (pin "1") (pinfunction "1_1") (pintype "unspecified"))
      (node (ref "C370") (pin "1") (pinfunction "1_1") (pintype "unspecified"))
      (node (ref "C371") (pin "1") (pinfunction "1_1") (pintype "unspecified"))
      (node (ref "C372") (pin "1") (pinfunction "1_1") (pintype "unspecified"))
      (node (ref "C373") (pin "1") (pinfunction "1_1") (pintype "unspecified"))
      (node (ref "C374") (pin "1") (pinfunction "1_1") (pintype "unspecified"))
      (node (ref "C375") (pin "1") (pinfunction "1_1") (pintype "unspecified"))
      (node (ref "C376") (pin "1") (pinfunction "1_1") (pintype "unspecified"))
      (node (ref "C377") (pin "2") (pinfunction "2_2") (pintype "unspecified"))
      (node (ref "C378") (pin "2") (pinfunction "2_2") (pintype "unspecified"))
      (node (ref "C379") (pin "2") (pinfunction "2_2") (pintype "unspecified"))
      (node (ref "C380") (pin "2") (pinfunction "2_2") (pintype "unspecified"))
      (node (ref "C382") (pin "1") (pinfunction "1_1") (pintype "unspecified"))
      (node (ref "C383") (pin "1") (pinfunction "1_1") (pintype "unspecified"))
      (node (ref "C384") (pin "1") (pinfunction "1_1") (pintype "input"))
      (node (ref "C385") (pin "1") (pinfunction "1_1") (pintype "unspecified"))
      (node (ref "C386") (pin "1") (pinfunction "1_1") (pintype "unspecified"))
      (node (ref "C387") (pin "1") (pinfunction "1_1") (pintype "unspecified"))
      (node (ref "C388") (pin "1") (pinfunction "1_1") (pintype "unspecified"))
      (node (ref "C6") (pin "1") (pinfunction "1_1") (pintype "unspecified"))
      (node (ref "C9") (pin "2") (pinfunction "2_2") (pintype "unspecified"))
      (node (ref "CN1") (pin "2") (pinfunction "2_2") (pintype "unspecified"))
      (node (ref "D1") (pin "2") (pinfunction "GND_2") (pintype "unspecified"))
      (node (ref "D5") (pin "2") (pinfunction "A_2") (pintype "input"))
      (node (ref "D6") (pin "1") (pinfunction "A_1") (pintype "input"))
      (node (ref "H1") (pin "1") (pinfunction "1_1") (pintype "input"))
      (node (ref "H10") (pin "3") (pinfunction "3_3") (pintype "unspecified"))
      (node (ref "H11") (pin "2") (pinfunction "2_2") (pintype "unspecified"))
      (node (ref "H12") (pin "3") (pinfunction "3_3") (pintype "unspecified"))
      (node (ref "H14") (pin "3") (pinfunction "3_3") (pintype "unspecified"))
      (node (ref "H14") (pin "4") (pinfunction "4_4") (pintype "unspecified"))
      (node (ref "H16") (pin "1") (pinfunction "1_1") (pintype "unspecified"))
      (node (ref "H2") (pin "1") (pinfunction "1_1") (pintype "input"))
      (node (ref "H3") (pin "1") (pinfunction "1_1") (pintype "input"))
      (node (ref "H4") (pin "1") (pinfunction "1_1") (pintype "input"))
      (node (ref "H6") (pin "1") (pinfunction "1_1") (pintype "unspecified"))
      (node (ref "H7") (pin "1") (pinfunction "1_1") (pintype "unspecified"))
      (node (ref "H8") (pin "1") (pinfunction "1_1") (pintype "unspecified"))
      (node (ref "H9") (pin "3") (pinfunction "3_3") (pintype "unspecified"))
      (node (ref "LED白") (pin "1") (pinfunction "-_1") (pintype "input"))
      (node (ref "LED红") (pin "2") (pinfunction "-_2") (pintype "unspecified"))
      (node (ref "LED绿") (pin "1") (pinfunction "K_1") (pintype "unspecified"))
      (node (ref "LED蓝") (pin "2") (pinfunction "-_2") (pintype "unspecified"))
      (node (ref "Q2") (pin "2") (pinfunction "E_2") (pintype "unspecified"))
      (node (ref "R1") (pin "2") (pinfunction "2_2") (pintype "input"))
      (node (ref "R15") (pin "2") (pinfunction "2_2") (pintype "input"))
      (node (ref "R19") (pin "2") (pinfunction "2_2") (pintype "input"))
      (node (ref "R2") (pin "2") (pinfunction "2_2") (pintype "input"))
      (node (ref "R29") (pin "2") (pinfunction "2_2") (pintype "unspecified"))
      (node (ref "SW1") (pin "1") (pinfunction "1_1") (pintype "unspecified"))
      (node (ref "SW1") (pin "2") (pinfunction "2_2") (pintype "unspecified"))
      (node (ref "SW2") (pin "1") (pinfunction "1_1") (pintype "unspecified"))
      (node (ref "SW2") (pin "2") (pinfunction "2_2") (pintype "unspecified"))
      (node (ref "SW3") (pin "1") (pinfunction "1_1") (pintype "unspecified"))
      (node (ref "SW3") (pin "2") (pinfunction "2_2") (pintype "unspecified"))
      (node (ref "U31") (pin "2") (pinfunction "VSS_2") (pintype "unspecified"))
      (node (ref "U34") (pin "2") (pinfunction "GND_2") (pintype "unspecified"))
      (node (ref "U36") (pin "4") (pinfunction "4_4") (pintype "unspecified"))
      (node (ref "U36") (pin "5") (pinfunction "5_5") (pintype "unspecified"))
      (node (ref "U37") (pin "2") (pinfunction "GND_2") (pintype "unspecified"))
      (node (ref "U37") (pin "25") (pinfunction "EPAD_25") (pintype "unspecified"))
      (node (ref "U40") (pin "2") (pinfunction "VSS_2") (pintype "unspecified"))
      (node (ref "U41") (pin "1") (pinfunction "GND_1") (pintype "unspecified"))
      (node (ref "U41") (pin "15") (pinfunction "GND_15") (pintype "unspecified"))
      (node (ref "U41") (pin "38") (pinfunction "GND_38") (pintype "unspecified"))
      (node (ref "U41") (pin "39") (pinfunction "GND_39") (pintype "unspecified"))
      (node (ref "U42") (pin "2") (pinfunction "VSS_2") (pintype "unspecified"))
      (node (ref "U43") (pin "6") (pinfunction "GND_6") (pintype "unspecified"))
      (node (ref "U43") (pin "9") (pinfunction "EP_9") (pintype "unspecified"))
      (node (ref "USB1") (pin "1") (pinfunction "GND_1") (pintype "unspecified"))
      (node (ref "USB1") (pin "12") (pinfunction "GND_12") (pintype "unspecified"))
      (node (ref "USB1") (pin "13") (pinfunction "SHELL_13") (pintype "unspecified"))
      (node (ref "USB1") (pin "14") (pinfunction "SHELL_14") (pintype "unspecified"))
    )
    (net (code "39") (name "Net-(D3-A)") (class "Default")
      (node (ref "D3") (pin "2") (pinfunction "A_2") (pintype "unspecified"))
      (node (ref "K1") (pin "2") (pinfunction "~_2") (pintype "unspecified"))
      (node (ref "Q2") (pin "3") (pinfunction "C_3") (pintype "unspecified"))
      (node (ref "U38") (pin "1") (pinfunction "K_1") (pintype "unspecified"))
    )
    (net (code "40") (name "Net-(D5-K)") (class "Default")
      (node (ref "C389") (pin "1") (pinfunction "1_1") (pintype "unspecified"))
      (node (ref "D5") (pin "1") (pinfunction "K_1") (pintype "input"))
      (node (ref "L12") (pin "1") (pinfunction "1_1") (pintype "unspecified"))
      (node (ref "U43") (pin "8") (pinfunction "PH_8") (pintype "unspecified"))
    )
    (net (code "41") (name "Net-(D7-A)") (class "Default")
      (node (ref "C385") (pin "2") (pinfunction "2_2") (pintype "unspecified"))
      (node (ref "C386") (pin "2") (pinfunction "2_2") (pintype "unspecified"))
      (node (ref "C387") (pin "2") (pinfunction "2_2") (pintype "unspecified"))
      (node (ref "C388") (pin "2") (pinfunction "2_2") (pintype "unspecified"))
      (node (ref "D7") (pin "2") (pinfunction "A_2") (pintype "input"))
      (node (ref "L12") (pin "2") (pinfunction "2_2") (pintype "unspecified"))
      (node (ref "R28") (pin "2") (pinfunction "2_2") (pintype "input"))
    )
    (net (code "42") (name "Net-(K1-~-Pad1)") (class "Default")
      (node (ref "K1") (pin "1") (pinfunction "~_1") (pintype "unspecified"))
      (node (ref "U39") (pin "3") (pinfunction "3_3") (pintype "unspecified"))
      (node (ref "U39") (pin "4") (pinfunction "4_4") (pintype "unspecified"))
    )
    (net (code "43") (name "Net-(K1-~-Pad3)") (class "Default")
      (node (ref "K1") (pin "3") (pinfunction "~_3") (pintype "unspecified"))
      (node (ref "U39") (pin "5") (pinfunction "5_5") (pintype "unspecified"))
      (node (ref "U39") (pin "6") (pinfunction "6_6") (pintype "unspecified"))
    )
    (net (code "44") (name "Net-(K1-~-Pad4)") (class "Default")
      (node (ref "K1") (pin "4") (pinfunction "~_4") (pintype "unspecified"))
      (node (ref "U39") (pin "1") (pinfunction "1_1") (pintype "unspecified"))
      (node (ref "U39") (pin "2") (pinfunction "2_2") (pintype "unspecified"))
    )
    (net (code "45") (name "Net-(LED1---Pad4)") (class "Default")
      (node (ref "LED1") (pin "4") (pinfunction "-_4") (pintype "unspecified"))
      (node (ref "R12") (pin "2") (pinfunction "2_2") (pintype "input"))
    )
    (net (code "46") (name "Net-(LED1---Pad5)") (class "Default")
      (node (ref "LED1") (pin "5") (pinfunction "-_5") (pintype "unspecified"))
      (node (ref "R13") (pin "2") (pinfunction "2_2") (pintype "input"))
    )
    (net (code "47") (name "Net-(LED1---Pad6)") (class "Default")
      (node (ref "LED1") (pin "6") (pinfunction "-_6") (pintype "unspecified"))
      (node (ref "R14") (pin "2") (pinfunction "2_2") (pintype "input"))
    )
    (net (code "48") (name "Net-(LED白-+)") (class "Default")
      (node (ref "LED白") (pin "2") (pinfunction "+_2") (pintype "input"))
      (node (ref "R7") (pin "2") (pinfunction "2_2") (pintype "input"))
    )
    (net (code "49") (name "Net-(LED红-+)") (class "Default")
      (node (ref "LED红") (pin "1") (pinfunction "+_1") (pintype "unspecified"))
      (node (ref "R24") (pin "1") (pinfunction "1_1") (pintype "input"))
    )
    (net (code "50") (name "Net-(LED绿-A)") (class "Default")
      (node (ref "LED绿") (pin "2") (pinfunction "A_2") (pintype "unspecified"))
      (node (ref "R23") (pin "1") (pinfunction "1_1") (pintype "input"))
    )
    (net (code "51") (name "Net-(LED蓝-+)") (class "Default")
      (node (ref "LED蓝") (pin "1") (pinfunction "+_1") (pintype "unspecified"))
      (node (ref "R11") (pin "1") (pinfunction "1_1") (pintype "input"))
    )
    (net (code "52") (name "Net-(Q2-B)") (class "Default")
      (node (ref "Q2") (pin "1") (pinfunction "B_1") (pintype "unspecified"))
      (node (ref "R19") (pin "1") (pinfunction "1_1") (pintype "input"))
      (node (ref "R20") (pin "2") (pinfunction "2_2") (pintype "input"))
    )
    (net (code "53") (name "Net-(R16-Pad1)") (class "Default")
      (node (ref "R16") (pin "1") (pinfunction "1_1") (pintype "input"))
      (node (ref "U36") (pin "2") (pinfunction "2_2") (pintype "unspecified"))
    )
    (net (code "54") (name "Net-(U34-S)") (class "Default")
      (node (ref "R15") (pin "1") (pinfunction "1_1") (pintype "input"))
      (node (ref "U34") (pin "8") (pinfunction "S_8") (pintype "unspecified"))
    )
    (net (code "55") (name "Net-(U37-D+)") (class "Default")
      (node (ref "D1") (pin "6") (pinfunction "I/O1_6") (pintype "unspecified"))
      (node (ref "U37") (pin "3") (pinfunction "D+_3") (pintype "unspecified"))
    )
    (net (code "56") (name "Net-(U37-D-)") (class "Default")
      (node (ref "D1") (pin "4") (pinfunction "I/O2_4") (pintype "unspecified"))
      (node (ref "U37") (pin "4") (pinfunction "D-_4") (pintype "unspecified"))
    )
    (net (code "57") (name "Net-(U37-RST#)") (class "Default")
      (node (ref "R17") (pin "2") (pinfunction "2_2") (pintype "input"))
      (node (ref "U37") (pin "9") (pinfunction "RST#_9") (pintype "unspecified"))
    )
    (net (code "58") (name "Net-(U37-RXD)") (class "Default")
      (node (ref "R5") (pin "1") (pinfunction "1_1") (pintype "input"))
      (node (ref "U37") (pin "20") (pinfunction "RXD_20") (pintype "unspecified"))
    )
    (net (code "59") (name "Net-(U37-TXD)") (class "Default")
      (node (ref "R4") (pin "1") (pinfunction "1_1") (pintype "input"))
      (node (ref "U37") (pin "21") (pinfunction "TXD_21") (pintype "unspecified"))
    )
    (net (code "60") (name "Net-(U37-VPP)") (class "Default")
      (node (ref "C6") (pin "2") (pinfunction "2_2") (pintype "unspecified"))
      (node (ref "U37") (pin "16") (pinfunction "VPP_16") (pintype "unspecified"))
    )
    (net (code "61") (name "Net-(U38-A)") (class "Default")
      (node (ref "R18") (pin "2") (pinfunction "2_2") (pintype "input"))
      (node (ref "U38") (pin "2") (pinfunction "A_2") (pintype "unspecified"))
    )
    (net (code "62") (name "Net-(U43-BOOT)") (class "Default")
      (node (ref "C389") (pin "2") (pinfunction "2_2") (pintype "unspecified"))
      (node (ref "U43") (pin "1") (pinfunction "BOOT_1") (pintype "unspecified"))
    )
    (net (code "63") (name "Net-(USB1-CC1)") (class "Default")
      (node (ref "R2") (pin "1") (pinfunction "1_1") (pintype "input"))
      (node (ref "USB1") (pin "4") (pinfunction "CC1_4") (pintype "unspecified"))
    )
    (net (code "64") (name "Net-(USB1-CC2)") (class "Default")
      (node (ref "R1") (pin "1") (pinfunction "1_1") (pintype "input"))
      (node (ref "USB1") (pin "10") (pinfunction "CC2_10") (pintype "unspecified"))
    )
    (net (code "65") (name "VCC") (class "Default")
      (node (ref "C382") (pin "2") (pinfunction "2_2") (pintype "unspecified"))
      (node (ref "C383") (pin "2") (pinfunction "2_2") (pintype "unspecified"))
      (node (ref "C384") (pin "2") (pinfunction "2_2") (pintype "input"))
      (node (ref "CN1") (pin "1") (pinfunction "1_1") (pintype "unspecified"))
      (node (ref "D6") (pin "2") (pinfunction "K_2") (pintype "input"))
      (node (ref "U43") (pin "7") (pinfunction "VIN_7") (pintype "unspecified"))
    )
    (net (code "66") (name "VDD") (class "Default")
      (node (ref "C359") (pin "2") (pinfunction "2_2") (pintype "unspecified"))
      (node (ref "C360") (pin "2") (pinfunction "2_2") (pintype "unspecified"))
      (node (ref "R17") (pin "1") (pinfunction "1_1") (pintype "input"))
      (node (ref "R7") (pin "1") (pinfunction "1_1") (pintype "input"))
      (node (ref "U37") (pin "5") (pinfunction "VIO_5") (pintype "unspecified"))
      (node (ref "U37") (pin "6") (pinfunction "VDD_6") (pintype "unspecified"))
    )
    (net (code "67") (name "unconnected-(H9-Pad4)") (class "Default")
      (node (ref "H9") (pin "4") (pinfunction "4_4") (pintype "unspecified+no_connect"))
    )
    (net (code "68") (name "unconnected-(H10-Pad4)") (class "Default")
      (node (ref "H10") (pin "4") (pinfunction "4_4") (pintype "unspecified+no_connect"))
    )
    (net (code "69") (name "unconnected-(U31-NC-Pad4)") (class "Default")
      (node (ref "U31") (pin "4") (pinfunction "NC_4") (pintype "unspecified+no_connect"))
    )
    (net (code "70") (name "unconnected-(U36-Pad3)") (class "Default")
      (node (ref "U36") (pin "3") (pinfunction "3_3") (pintype "unspecified+no_connect"))
    )
    (net (code "71") (name "unconnected-(U37-CTS-Pad18)") (class "Default")
      (node (ref "U37") (pin "18") (pinfunction "CTS_18") (pintype "unspecified+no_connect"))
    )
    (net (code "72") (name "unconnected-(U37-DCD-Pad24)") (class "Default")
      (node (ref "U37") (pin "24") (pinfunction "DCD_24") (pintype "unspecified+no_connect"))
    )
    (net (code "73") (name "unconnected-(U37-DSR-Pad22)") (class "Default")
      (node (ref "U37") (pin "22") (pinfunction "DSR_22") (pintype "unspecified+no_connect"))
    )
    (net (code "74") (name "unconnected-(U37-GPIO.0-Pad14)") (class "Default")
      (node (ref "U37") (pin "14") (pinfunction "GPIO.0_14") (pintype "unspecified+no_connect"))
    )
    (net (code "75") (name "unconnected-(U37-GPIO.1-Pad13)") (class "Default")
      (node (ref "U37") (pin "13") (pinfunction "GPIO.1_13") (pintype "unspecified+no_connect"))
    )
    (net (code "76") (name "unconnected-(U37-GPIO.2-Pad12)") (class "Default")
      (node (ref "U37") (pin "12") (pinfunction "GPIO.2_12") (pintype "unspecified+no_connect"))
    )
    (net (code "77") (name "unconnected-(U37-GPIO.3-Pad11)") (class "Default")
      (node (ref "U37") (pin "11") (pinfunction "GPIO.3_11") (pintype "unspecified+no_connect"))
    )
    (net (code "78") (name "unconnected-(U37-NC-Pad10)") (class "Default")
      (node (ref "U37") (pin "10") (pinfunction "NC_10") (pintype "unspecified+no_connect"))
    )
    (net (code "79") (name "unconnected-(U37-RI-Pad1)") (class "Default")
      (node (ref "U37") (pin "1") (pinfunction "RI_1") (pintype "unspecified+no_connect"))
    )
    (net (code "80") (name "unconnected-(U37-SUSPEND#-Pad15)") (class "Default")
      (node (ref "U37") (pin "15") (pinfunction "SUSPEND#_15") (pintype "unspecified+no_connect"))
    )
    (net (code "81") (name "unconnected-(U37-SUSPEND-Pad17)") (class "Default")
      (node (ref "U37") (pin "17") (pinfunction "SUSPEND_17") (pintype "unspecified+no_connect"))
    )
    (net (code "82") (name "unconnected-(U40-NC-Pad4)") (class "Default")
      (node (ref "U40") (pin "4") (pinfunction "NC_4") (pintype "unspecified+no_connect"))
    )
    (net (code "83") (name "unconnected-(U41-CLK-Pad20)") (class "Default")
      (node (ref "U41") (pin "20") (pinfunction "CLK_20") (pintype "unspecified+no_connect"))
    )
    (net (code "84") (name "unconnected-(U41-CMD-Pad19)") (class "Default")
      (node (ref "U41") (pin "19") (pinfunction "CMD_19") (pintype "unspecified+no_connect"))
    )
    (net (code "85") (name "unconnected-(U41-NC-Pad32)") (class "Default")
      (node (ref "U41") (pin "32") (pinfunction "NC_32") (pintype "unspecified+no_connect"))
    )
    (net (code "86") (name "unconnected-(U41-SD0-Pad21)") (class "Default")
      (node (ref "U41") (pin "21") (pinfunction "SD0_21") (pintype "unspecified+no_connect"))
    )
    (net (code "87") (name "unconnected-(U41-SD1-Pad22)") (class "Default")
      (node (ref "U41") (pin "22") (pinfunction "SD1_22") (pintype "unspecified+no_connect"))
    )
    (net (code "88") (name "unconnected-(U41-SD2-Pad17)") (class "Default")
      (node (ref "U41") (pin "17") (pinfunction "SD2_17") (pintype "unspecified+no_connect"))
    )
    (net (code "89") (name "unconnected-(U41-SD3-Pad18)") (class "Default")
      (node (ref "U41") (pin "18") (pinfunction "SD3_18") (pintype "unspecified+no_connect"))
    )
    (net (code "90") (name "unconnected-(U41-SENSOR_VN-Pad5)") (class "Default")
      (node (ref "U41") (pin "5") (pinfunction "SENSOR_VN_5") (pintype "unspecified+no_connect"))
    )
    (net (code "91") (name "unconnected-(U41-SENSOR_VP-Pad4)") (class "Default")
      (node (ref "U41") (pin "4") (pinfunction "SENSOR_VP_4") (pintype "unspecified+no_connect"))
    )
    (net (code "92") (name "unconnected-(U42-NC-Pad4)") (class "Default")
      (node (ref "U42") (pin "4") (pinfunction "NC_4") (pintype "unspecified+no_connect"))
    )
    (net (code "93") (name "unconnected-(U43-ENA-Pad5)") (class "Default")
      (node (ref "U43") (pin "5") (pinfunction "ENA_5") (pintype "unspecified+no_connect"))
    )
    (net (code "94") (name "unconnected-(U43-NC-Pad2)") (class "Default")
      (node (ref "U43") (pin "2") (pinfunction "NC_2") (pintype "unspecified+no_connect"))
    )
    (net (code "95") (name "unconnected-(U43-NC-Pad3)") (class "Default")
      (node (ref "U43") (pin "3") (pinfunction "NC_3") (pintype "unspecified+no_connect"))
    )
    (net (code "96") (name "unconnected-(USB1-SBU1-Pad9)") (class "Default")
      (node (ref "USB1") (pin "9") (pinfunction "SBU1_9") (pintype "unspecified+no_connect"))
    )
    (net (code "97") (name "unconnected-(USB1-SBU2-Pad3)") (class "Default")
      (node (ref "USB1") (pin "3") (pinfunction "SBU2_3") (pintype "unspecified+no_connect"))
    )
  )
)
